# design.net
KiCad netlist of a schematic drawn in Altium Designer
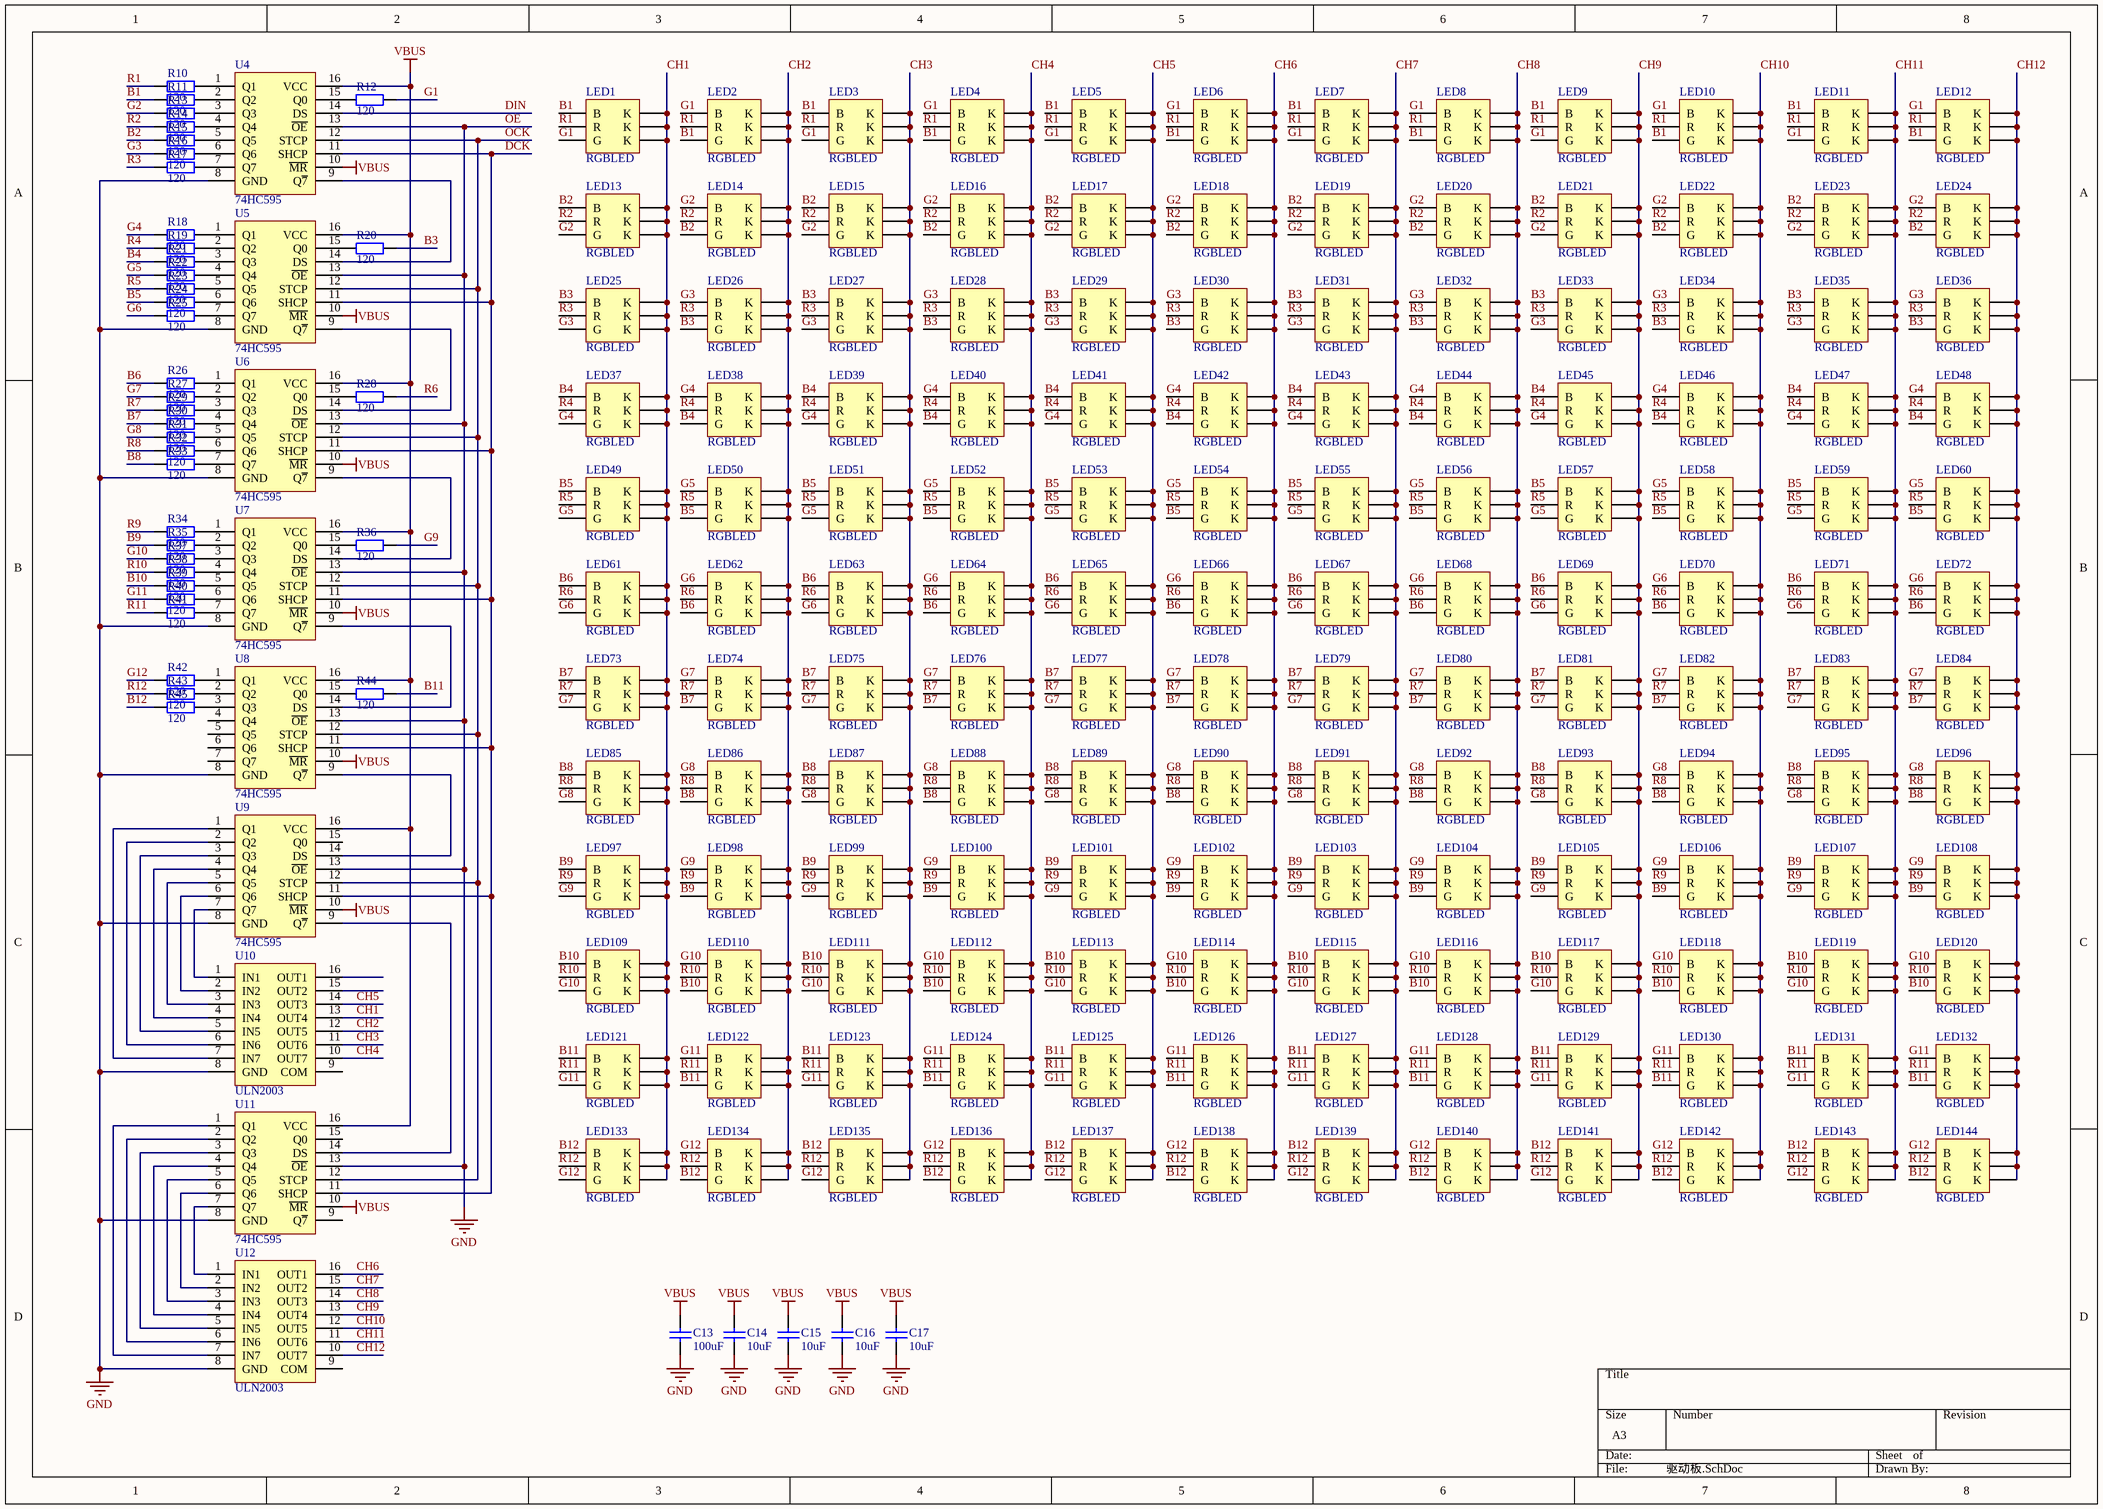
[diagram p0: 驱动板.SchDoc]

(export (version "E")
  (design (tool "Eeschema 10.0.6"))
  (components
    (comp (ref "C13")
      (value "100uF")
      (footprint "2512")
      (description "Capacitor")
      (fields (field (name "PUBLISHER") "Altium Limited"))
      (libsource (lib "yitiandelan") (part "Cap"))
    )
    (comp (ref "C14")
      (value "10uF")
      (footprint "0805")
      (description "Capacitor")
      (fields (field (name "PUBLISHER") "Altium Limited"))
      (libsource (lib "yitiandelan") (part "Cap"))
    )
    (comp (ref "C15")
      (value "10uF")
      (footprint "0805")
      (description "Capacitor")
      (fields (field (name "PUBLISHER") "Altium Limited"))
      (libsource (lib "yitiandelan") (part "Cap"))
    )
    (comp (ref "C16")
      (value "10uF")
      (footprint "0805")
      (description "Capacitor")
      (fields (field (name "PUBLISHER") "Altium Limited"))
      (libsource (lib "yitiandelan") (part "Cap"))
    )
    (comp (ref "C17")
      (value "10uF")
      (footprint "0805")
      (description "Capacitor")
      (fields (field (name "PUBLISHER") "Altium Limited"))
      (libsource (lib "yitiandelan") (part "Cap"))
    )
    (comp (ref "LED1") (value "RGBLED") (footprint "5050") (libsource (lib "yitiandelan") (part "RGBLED")))
    (comp (ref "LED2") (value "RGBLED") (footprint "5050") (libsource (lib "yitiandelan") (part "RGBLED")))
    (comp (ref "LED3") (value "RGBLED") (footprint "5050") (libsource (lib "yitiandelan") (part "RGBLED")))
    (comp (ref "LED4") (value "RGBLED") (footprint "5050") (libsource (lib "yitiandelan") (part "RGBLED")))
    (comp (ref "LED5") (value "RGBLED") (footprint "5050") (libsource (lib "yitiandelan") (part "RGBLED")))
    (comp (ref "LED6") (value "RGBLED") (footprint "5050") (libsource (lib "yitiandelan") (part "RGBLED")))
    (comp (ref "LED7") (value "RGBLED") (footprint "5050") (libsource (lib "yitiandelan") (part "RGBLED")))
    (comp (ref "LED8") (value "RGBLED") (footprint "5050") (libsource (lib "yitiandelan") (part "RGBLED")))
    (comp (ref "LED9") (value "RGBLED") (footprint "5050") (libsource (lib "yitiandelan") (part "RGBLED")))
    (comp (ref "LED10") (value "RGBLED") (footprint "5050") (libsource (lib "yitiandelan") (part "RGBLED")))
    (comp (ref "LED11") (value "RGBLED") (footprint "5050") (libsource (lib "yitiandelan") (part "RGBLED")))
    (comp (ref "LED12") (value "RGBLED") (footprint "5050") (libsource (lib "yitiandelan") (part "RGBLED")))
    (comp (ref "LED13") (value "RGBLED") (footprint "5050") (libsource (lib "yitiandelan") (part "RGBLED")))
    (comp (ref "LED14") (value "RGBLED") (footprint "5050") (libsource (lib "yitiandelan") (part "RGBLED")))
    (comp (ref "LED15") (value "RGBLED") (footprint "5050") (libsource (lib "yitiandelan") (part "RGBLED")))
    (comp (ref "LED16") (value "RGBLED") (footprint "5050") (libsource (lib "yitiandelan") (part "RGBLED")))
    (comp (ref "LED17") (value "RGBLED") (footprint "5050") (libsource (lib "yitiandelan") (part "RGBLED")))
    (comp (ref "LED18") (value "RGBLED") (footprint "5050") (libsource (lib "yitiandelan") (part "RGBLED")))
    (comp (ref "LED19") (value "RGBLED") (footprint "5050") (libsource (lib "yitiandelan") (part "RGBLED")))
    (comp (ref "LED20") (value "RGBLED") (footprint "5050") (libsource (lib "yitiandelan") (part "RGBLED")))
    (comp (ref "LED21") (value "RGBLED") (footprint "5050") (libsource (lib "yitiandelan") (part "RGBLED")))
    (comp (ref "LED22") (value "RGBLED") (footprint "5050") (libsource (lib "yitiandelan") (part "RGBLED")))
    (comp (ref "LED23") (value "RGBLED") (footprint "5050") (libsource (lib "yitiandelan") (part "RGBLED")))
    (comp (ref "LED24") (value "RGBLED") (footprint "5050") (libsource (lib "yitiandelan") (part "RGBLED")))
    (comp (ref "LED25") (value "RGBLED") (footprint "5050") (libsource (lib "yitiandelan") (part "RGBLED")))
    (comp (ref "LED26") (value "RGBLED") (footprint "5050") (libsource (lib "yitiandelan") (part "RGBLED")))
    (comp (ref "LED27") (value "RGBLED") (footprint "5050") (libsource (lib "yitiandelan") (part "RGBLED")))
    (comp (ref "LED28") (value "RGBLED") (footprint "5050") (libsource (lib "yitiandelan") (part "RGBLED")))
    (comp (ref "LED29") (value "RGBLED") (footprint "5050") (libsource (lib "yitiandelan") (part "RGBLED")))
    (comp (ref "LED30") (value "RGBLED") (footprint "5050") (libsource (lib "yitiandelan") (part "RGBLED")))
    (comp (ref "LED31") (value "RGBLED") (footprint "5050") (libsource (lib "yitiandelan") (part "RGBLED")))
    (comp (ref "LED32") (value "RGBLED") (footprint "5050") (libsource (lib "yitiandelan") (part "RGBLED")))
    (comp (ref "LED33") (value "RGBLED") (footprint "5050") (libsource (lib "yitiandelan") (part "RGBLED")))
    (comp (ref "LED34") (value "RGBLED") (footprint "5050") (libsource (lib "yitiandelan") (part "RGBLED")))
    (comp (ref "LED35") (value "RGBLED") (footprint "5050") (libsource (lib "yitiandelan") (part "RGBLED")))
    (comp (ref "LED36") (value "RGBLED") (footprint "5050") (libsource (lib "yitiandelan") (part "RGBLED")))
    (comp (ref "LED37") (value "RGBLED") (footprint "5050") (libsource (lib "yitiandelan") (part "RGBLED")))
    (comp (ref "LED38") (value "RGBLED") (footprint "5050") (libsource (lib "yitiandelan") (part "RGBLED")))
    (comp (ref "LED39") (value "RGBLED") (footprint "5050") (libsource (lib "yitiandelan") (part "RGBLED")))
    (comp (ref "LED40") (value "RGBLED") (footprint "5050") (libsource (lib "yitiandelan") (part "RGBLED")))
    (comp (ref "LED41") (value "RGBLED") (footprint "5050") (libsource (lib "yitiandelan") (part "RGBLED")))
    (comp (ref "LED42") (value "RGBLED") (footprint "5050") (libsource (lib "yitiandelan") (part "RGBLED")))
    (comp (ref "LED43") (value "RGBLED") (footprint "5050") (libsource (lib "yitiandelan") (part "RGBLED")))
    (comp (ref "LED44") (value "RGBLED") (footprint "5050") (libsource (lib "yitiandelan") (part "RGBLED")))
    (comp (ref "LED45") (value "RGBLED") (footprint "5050") (libsource (lib "yitiandelan") (part "RGBLED")))
    (comp (ref "LED46") (value "RGBLED") (footprint "5050") (libsource (lib "yitiandelan") (part "RGBLED")))
    (comp (ref "LED47") (value "RGBLED") (footprint "5050") (libsource (lib "yitiandelan") (part "RGBLED")))
    (comp (ref "LED48") (value "RGBLED") (footprint "5050") (libsource (lib "yitiandelan") (part "RGBLED")))
    (comp (ref "LED49") (value "RGBLED") (footprint "5050") (libsource (lib "yitiandelan") (part "RGBLED")))
    (comp (ref "LED50") (value "RGBLED") (footprint "5050") (libsource (lib "yitiandelan") (part "RGBLED")))
    (comp (ref "LED51") (value "RGBLED") (footprint "5050") (libsource (lib "yitiandelan") (part "RGBLED")))
    (comp (ref "LED52") (value "RGBLED") (footprint "5050") (libsource (lib "yitiandelan") (part "RGBLED")))
    (comp (ref "LED53") (value "RGBLED") (footprint "5050") (libsource (lib "yitiandelan") (part "RGBLED")))
    (comp (ref "LED54") (value "RGBLED") (footprint "5050") (libsource (lib "yitiandelan") (part "RGBLED")))
    (comp (ref "LED55") (value "RGBLED") (footprint "5050") (libsource (lib "yitiandelan") (part "RGBLED")))
    (comp (ref "LED56") (value "RGBLED") (footprint "5050") (libsource (lib "yitiandelan") (part "RGBLED")))
    (comp (ref "LED57") (value "RGBLED") (footprint "5050") (libsource (lib "yitiandelan") (part "RGBLED")))
    (comp (ref "LED58") (value "RGBLED") (footprint "5050") (libsource (lib "yitiandelan") (part "RGBLED")))
    (comp (ref "LED59") (value "RGBLED") (footprint "5050") (libsource (lib "yitiandelan") (part "RGBLED")))
    (comp (ref "LED60") (value "RGBLED") (footprint "5050") (libsource (lib "yitiandelan") (part "RGBLED")))
    (comp (ref "LED61") (value "RGBLED") (footprint "5050") (libsource (lib "yitiandelan") (part "RGBLED")))
    (comp (ref "LED62") (value "RGBLED") (footprint "5050") (libsource (lib "yitiandelan") (part "RGBLED")))
    (comp (ref "LED63") (value "RGBLED") (footprint "5050") (libsource (lib "yitiandelan") (part "RGBLED")))
    (comp (ref "LED64") (value "RGBLED") (footprint "5050") (libsource (lib "yitiandelan") (part "RGBLED")))
    (comp (ref "LED65") (value "RGBLED") (footprint "5050") (libsource (lib "yitiandelan") (part "RGBLED")))
    (comp (ref "LED66") (value "RGBLED") (footprint "5050") (libsource (lib "yitiandelan") (part "RGBLED")))
    (comp (ref "LED67") (value "RGBLED") (footprint "5050") (libsource (lib "yitiandelan") (part "RGBLED")))
    (comp (ref "LED68") (value "RGBLED") (footprint "5050") (libsource (lib "yitiandelan") (part "RGBLED")))
    (comp (ref "LED69") (value "RGBLED") (footprint "5050") (libsource (lib "yitiandelan") (part "RGBLED")))
    (comp (ref "LED70") (value "RGBLED") (footprint "5050") (libsource (lib "yitiandelan") (part "RGBLED")))
    (comp (ref "LED71") (value "RGBLED") (footprint "5050") (libsource (lib "yitiandelan") (part "RGBLED")))
    (comp (ref "LED72") (value "RGBLED") (footprint "5050") (libsource (lib "yitiandelan") (part "RGBLED")))
    (comp (ref "LED73") (value "RGBLED") (footprint "5050") (libsource (lib "yitiandelan") (part "RGBLED")))
    (comp (ref "LED74") (value "RGBLED") (footprint "5050") (libsource (lib "yitiandelan") (part "RGBLED")))
    (comp (ref "LED75") (value "RGBLED") (footprint "5050") (libsource (lib "yitiandelan") (part "RGBLED")))
    (comp (ref "LED76") (value "RGBLED") (footprint "5050") (libsource (lib "yitiandelan") (part "RGBLED")))
    (comp (ref "LED77") (value "RGBLED") (footprint "5050") (libsource (lib "yitiandelan") (part "RGBLED")))
    (comp (ref "LED78") (value "RGBLED") (footprint "5050") (libsource (lib "yitiandelan") (part "RGBLED")))
    (comp (ref "LED79") (value "RGBLED") (footprint "5050") (libsource (lib "yitiandelan") (part "RGBLED")))
    (comp (ref "LED80") (value "RGBLED") (footprint "5050") (libsource (lib "yitiandelan") (part "RGBLED")))
    (comp (ref "LED81") (value "RGBLED") (footprint "5050") (libsource (lib "yitiandelan") (part "RGBLED")))
    (comp (ref "LED82") (value "RGBLED") (footprint "5050") (libsource (lib "yitiandelan") (part "RGBLED")))
    (comp (ref "LED83") (value "RGBLED") (footprint "5050") (libsource (lib "yitiandelan") (part "RGBLED")))
    (comp (ref "LED84") (value "RGBLED") (footprint "5050") (libsource (lib "yitiandelan") (part "RGBLED")))
    (comp (ref "LED85") (value "RGBLED") (footprint "5050") (libsource (lib "yitiandelan") (part "RGBLED")))
    (comp (ref "LED86") (value "RGBLED") (footprint "5050") (libsource (lib "yitiandelan") (part "RGBLED")))
    (comp (ref "LED87") (value "RGBLED") (footprint "5050") (libsource (lib "yitiandelan") (part "RGBLED")))
    (comp (ref "LED88") (value "RGBLED") (footprint "5050") (libsource (lib "yitiandelan") (part "RGBLED")))
    (comp (ref "LED89") (value "RGBLED") (footprint "5050") (libsource (lib "yitiandelan") (part "RGBLED")))
    (comp (ref "LED90") (value "RGBLED") (footprint "5050") (libsource (lib "yitiandelan") (part "RGBLED")))
    (comp (ref "LED91") (value "RGBLED") (footprint "5050") (libsource (lib "yitiandelan") (part "RGBLED")))
    (comp (ref "LED92") (value "RGBLED") (footprint "5050") (libsource (lib "yitiandelan") (part "RGBLED")))
    (comp (ref "LED93") (value "RGBLED") (footprint "5050") (libsource (lib "yitiandelan") (part "RGBLED")))
    (comp (ref "LED94") (value "RGBLED") (footprint "5050") (libsource (lib "yitiandelan") (part "RGBLED")))
    (comp (ref "LED95") (value "RGBLED") (footprint "5050") (libsource (lib "yitiandelan") (part "RGBLED")))
    (comp (ref "LED96") (value "RGBLED") (footprint "5050") (libsource (lib "yitiandelan") (part "RGBLED")))
    (comp (ref "LED97") (value "RGBLED") (footprint "5050") (libsource (lib "yitiandelan") (part "RGBLED")))
    (comp (ref "LED98") (value "RGBLED") (footprint "5050") (libsource (lib "yitiandelan") (part "RGBLED")))
    (comp (ref "LED99") (value "RGBLED") (footprint "5050") (libsource (lib "yitiandelan") (part "RGBLED")))
    (comp (ref "LED100") (value "RGBLED") (footprint "5050") (libsource (lib "yitiandelan") (part "RGBLED")))
    (comp (ref "LED101") (value "RGBLED") (footprint "5050") (libsource (lib "yitiandelan") (part "RGBLED")))
    (comp (ref "LED102") (value "RGBLED") (footprint "5050") (libsource (lib "yitiandelan") (part "RGBLED")))
    (comp (ref "LED103") (value "RGBLED") (footprint "5050") (libsource (lib "yitiandelan") (part "RGBLED")))
    (comp (ref "LED104") (value "RGBLED") (footprint "5050") (libsource (lib "yitiandelan") (part "RGBLED")))
    (comp (ref "LED105") (value "RGBLED") (footprint "5050") (libsource (lib "yitiandelan") (part "RGBLED")))
    (comp (ref "LED106") (value "RGBLED") (footprint "5050") (libsource (lib "yitiandelan") (part "RGBLED")))
    (comp (ref "LED107") (value "RGBLED") (footprint "5050") (libsource (lib "yitiandelan") (part "RGBLED")))
    (comp (ref "LED108") (value "RGBLED") (footprint "5050") (libsource (lib "yitiandelan") (part "RGBLED")))
    (comp (ref "LED109") (value "RGBLED") (footprint "5050") (libsource (lib "yitiandelan") (part "RGBLED")))
    (comp (ref "LED110") (value "RGBLED") (footprint "5050") (libsource (lib "yitiandelan") (part "RGBLED")))
    (comp (ref "LED111") (value "RGBLED") (footprint "5050") (libsource (lib "yitiandelan") (part "RGBLED")))
    (comp (ref "LED112") (value "RGBLED") (footprint "5050") (libsource (lib "yitiandelan") (part "RGBLED")))
    (comp (ref "LED113") (value "RGBLED") (footprint "5050") (libsource (lib "yitiandelan") (part "RGBLED")))
    (comp (ref "LED114") (value "RGBLED") (footprint "5050") (libsource (lib "yitiandelan") (part "RGBLED")))
    (comp (ref "LED115") (value "RGBLED") (footprint "5050") (libsource (lib "yitiandelan") (part "RGBLED")))
    (comp (ref "LED116") (value "RGBLED") (footprint "5050") (libsource (lib "yitiandelan") (part "RGBLED")))
    (comp (ref "LED117") (value "RGBLED") (footprint "5050") (libsource (lib "yitiandelan") (part "RGBLED")))
    (comp (ref "LED118") (value "RGBLED") (footprint "5050") (libsource (lib "yitiandelan") (part "RGBLED")))
    (comp (ref "LED119") (value "RGBLED") (footprint "5050") (libsource (lib "yitiandelan") (part "RGBLED")))
    (comp (ref "LED120") (value "RGBLED") (footprint "5050") (libsource (lib "yitiandelan") (part "RGBLED")))
    (comp (ref "LED121") (value "RGBLED") (footprint "5050") (libsource (lib "yitiandelan") (part "RGBLED")))
    (comp (ref "LED122") (value "RGBLED") (footprint "5050") (libsource (lib "yitiandelan") (part "RGBLED")))
    (comp (ref "LED123") (value "RGBLED") (footprint "5050") (libsource (lib "yitiandelan") (part "RGBLED")))
    (comp (ref "LED124") (value "RGBLED") (footprint "5050") (libsource (lib "yitiandelan") (part "RGBLED")))
    (comp (ref "LED125") (value "RGBLED") (footprint "5050") (libsource (lib "yitiandelan") (part "RGBLED")))
    (comp (ref "LED126") (value "RGBLED") (footprint "5050") (libsource (lib "yitiandelan") (part "RGBLED")))
    (comp (ref "LED127") (value "RGBLED") (footprint "5050") (libsource (lib "yitiandelan") (part "RGBLED")))
    (comp (ref "LED128") (value "RGBLED") (footprint "5050") (libsource (lib "yitiandelan") (part "RGBLED")))
    (comp (ref "LED129") (value "RGBLED") (footprint "5050") (libsource (lib "yitiandelan") (part "RGBLED")))
    (comp (ref "LED130") (value "RGBLED") (footprint "5050") (libsource (lib "yitiandelan") (part "RGBLED")))
    (comp (ref "LED131") (value "RGBLED") (footprint "5050") (libsource (lib "yitiandelan") (part "RGBLED")))
    (comp (ref "LED132") (value "RGBLED") (footprint "5050") (libsource (lib "yitiandelan") (part "RGBLED")))
    (comp (ref "LED133") (value "RGBLED") (footprint "5050") (libsource (lib "yitiandelan") (part "RGBLED")))
    (comp (ref "LED134") (value "RGBLED") (footprint "5050") (libsource (lib "yitiandelan") (part "RGBLED")))
    (comp (ref "LED135") (value "RGBLED") (footprint "5050") (libsource (lib "yitiandelan") (part "RGBLED")))
    (comp (ref "LED136") (value "RGBLED") (footprint "5050") (libsource (lib "yitiandelan") (part "RGBLED")))
    (comp (ref "LED137") (value "RGBLED") (footprint "5050") (libsource (lib "yitiandelan") (part "RGBLED")))
    (comp (ref "LED138") (value "RGBLED") (footprint "5050") (libsource (lib "yitiandelan") (part "RGBLED")))
    (comp (ref "LED139") (value "RGBLED") (footprint "5050") (libsource (lib "yitiandelan") (part "RGBLED")))
    (comp (ref "LED140") (value "RGBLED") (footprint "5050") (libsource (lib "yitiandelan") (part "RGBLED")))
    (comp (ref "LED141") (value "RGBLED") (footprint "5050") (libsource (lib "yitiandelan") (part "RGBLED")))
    (comp (ref "LED142") (value "RGBLED") (footprint "5050") (libsource (lib "yitiandelan") (part "RGBLED")))
    (comp (ref "LED143") (value "RGBLED") (footprint "5050") (libsource (lib "yitiandelan") (part "RGBLED")))
    (comp (ref "LED144") (value "RGBLED") (footprint "5050") (libsource (lib "yitiandelan") (part "RGBLED")))
    (comp (ref "R10")
      (value "120")
      (footprint "0805")
      (description "Resistor")
      (fields (field (name "PUBLISHER") "Altium Limited"))
      (libsource (lib "yitiandelan") (part "Res2"))
    )
    (comp (ref "R11")
      (value "120")
      (footprint "0805")
      (description "Resistor")
      (fields (field (name "PUBLISHER") "Altium Limited"))
      (libsource (lib "yitiandelan") (part "Res2"))
    )
    (comp (ref "R12")
      (value "120")
      (footprint "0805")
      (description "Resistor")
      (fields (field (name "PUBLISHER") "Altium Limited"))
      (libsource (lib "yitiandelan") (part "Res2"))
    )
    (comp (ref "R13")
      (value "120")
      (footprint "0805")
      (description "Resistor")
      (fields (field (name "PUBLISHER") "Altium Limited"))
      (libsource (lib "yitiandelan") (part "Res2"))
    )
    (comp (ref "R14")
      (value "120")
      (footprint "0805")
      (description "Resistor")
      (fields (field (name "PUBLISHER") "Altium Limited"))
      (libsource (lib "yitiandelan") (part "Res2"))
    )
    (comp (ref "R15")
      (value "120")
      (footprint "0805")
      (description "Resistor")
      (fields (field (name "PUBLISHER") "Altium Limited"))
      (libsource (lib "yitiandelan") (part "Res2"))
    )
    (comp (ref "R16")
      (value "120")
      (footprint "0805")
      (description "Resistor")
      (fields (field (name "PUBLISHER") "Altium Limited"))
      (libsource (lib "yitiandelan") (part "Res2"))
    )
    (comp (ref "R17")
      (value "120")
      (footprint "0805")
      (description "Resistor")
      (fields (field (name "PUBLISHER") "Altium Limited"))
      (libsource (lib "yitiandelan") (part "Res2"))
    )
    (comp (ref "R18")
      (value "120")
      (footprint "0805")
      (description "Resistor")
      (fields (field (name "PUBLISHER") "Altium Limited"))
      (libsource (lib "yitiandelan") (part "Res2"))
    )
    (comp (ref "R19")
      (value "120")
      (footprint "0805")
      (description "Resistor")
      (fields (field (name "PUBLISHER") "Altium Limited"))
      (libsource (lib "yitiandelan") (part "Res2"))
    )
    (comp (ref "R20")
      (value "120")
      (footprint "0805")
      (description "Resistor")
      (fields (field (name "PUBLISHER") "Altium Limited"))
      (libsource (lib "yitiandelan") (part "Res2"))
    )
    (comp (ref "R21")
      (value "120")
      (footprint "0805")
      (description "Resistor")
      (fields (field (name "PUBLISHER") "Altium Limited"))
      (libsource (lib "yitiandelan") (part "Res2"))
    )
    (comp (ref "R22")
      (value "120")
      (footprint "0805")
      (description "Resistor")
      (fields (field (name "PUBLISHER") "Altium Limited"))
      (libsource (lib "yitiandelan") (part "Res2"))
    )
    (comp (ref "R23")
      (value "120")
      (footprint "0805")
      (description "Resistor")
      (fields (field (name "PUBLISHER") "Altium Limited"))
      (libsource (lib "yitiandelan") (part "Res2"))
    )
    (comp (ref "R24")
      (value "120")
      (footprint "0805")
      (description "Resistor")
      (fields (field (name "PUBLISHER") "Altium Limited"))
      (libsource (lib "yitiandelan") (part "Res2"))
    )
    (comp (ref "R25")
      (value "120")
      (footprint "0805")
      (description "Resistor")
      (fields (field (name "PUBLISHER") "Altium Limited"))
      (libsource (lib "yitiandelan") (part "Res2"))
    )
    (comp (ref "R26")
      (value "120")
      (footprint "0805")
      (description "Resistor")
      (fields (field (name "PUBLISHER") "Altium Limited"))
      (libsource (lib "yitiandelan") (part "Res2"))
    )
    (comp (ref "R27")
      (value "120")
      (footprint "0805")
      (description "Resistor")
      (fields (field (name "PUBLISHER") "Altium Limited"))
      (libsource (lib "yitiandelan") (part "Res2"))
    )
    (comp (ref "R28")
      (value "120")
      (footprint "0805")
      (description "Resistor")
      (fields (field (name "PUBLISHER") "Altium Limited"))
      (libsource (lib "yitiandelan") (part "Res2"))
    )
    (comp (ref "R29")
      (value "120")
      (footprint "0805")
      (description "Resistor")
      (fields (field (name "PUBLISHER") "Altium Limited"))
      (libsource (lib "yitiandelan") (part "Res2"))
    )
    (comp (ref "R30")
      (value "120")
      (footprint "0805")
      (description "Resistor")
      (fields (field (name "PUBLISHER") "Altium Limited"))
      (libsource (lib "yitiandelan") (part "Res2"))
    )
    (comp (ref "R31")
      (value "120")
      (footprint "0805")
      (description "Resistor")
      (fields (field (name "PUBLISHER") "Altium Limited"))
      (libsource (lib "yitiandelan") (part "Res2"))
    )
    (comp (ref "R32")
      (value "120")
      (footprint "0805")
      (description "Resistor")
      (fields (field (name "PUBLISHER") "Altium Limited"))
      (libsource (lib "yitiandelan") (part "Res2"))
    )
    (comp (ref "R33")
      (value "120")
      (footprint "0805")
      (description "Resistor")
      (fields (field (name "PUBLISHER") "Altium Limited"))
      (libsource (lib "yitiandelan") (part "Res2"))
    )
    (comp (ref "R34")
      (value "120")
      (footprint "0805")
      (description "Resistor")
      (fields (field (name "PUBLISHER") "Altium Limited"))
      (libsource (lib "yitiandelan") (part "Res2"))
    )
    (comp (ref "R35")
      (value "120")
      (footprint "0805")
      (description "Resistor")
      (fields (field (name "PUBLISHER") "Altium Limited"))
      (libsource (lib "yitiandelan") (part "Res2"))
    )
    (comp (ref "R36")
      (value "120")
      (footprint "0805")
      (description "Resistor")
      (fields (field (name "PUBLISHER") "Altium Limited"))
      (libsource (lib "yitiandelan") (part "Res2"))
    )
    (comp (ref "R37")
      (value "120")
      (footprint "0805")
      (description "Resistor")
      (fields (field (name "PUBLISHER") "Altium Limited"))
      (libsource (lib "yitiandelan") (part "Res2"))
    )
    (comp (ref "R38")
      (value "120")
      (footprint "0805")
      (description "Resistor")
      (fields (field (name "PUBLISHER") "Altium Limited"))
      (libsource (lib "yitiandelan") (part "Res2"))
    )
    (comp (ref "R39")
      (value "120")
      (footprint "0805")
      (description "Resistor")
      (fields (field (name "PUBLISHER") "Altium Limited"))
      (libsource (lib "yitiandelan") (part "Res2"))
    )
    (comp (ref "R40")
      (value "120")
      (footprint "0805")
      (description "Resistor")
      (fields (field (name "PUBLISHER") "Altium Limited"))
      (libsource (lib "yitiandelan") (part "Res2"))
    )
    (comp (ref "R41")
      (value "120")
      (footprint "0805")
      (description "Resistor")
      (fields (field (name "PUBLISHER") "Altium Limited"))
      (libsource (lib "yitiandelan") (part "Res2"))
    )
    (comp (ref "R42")
      (value "120")
      (footprint "0805")
      (description "Resistor")
      (fields (field (name "PUBLISHER") "Altium Limited"))
      (libsource (lib "yitiandelan") (part "Res2"))
    )
    (comp (ref "R43")
      (value "120")
      (footprint "0805")
      (description "Resistor")
      (fields (field (name "PUBLISHER") "Altium Limited"))
      (libsource (lib "yitiandelan") (part "Res2"))
    )
    (comp (ref "R44")
      (value "120")
      (footprint "0805")
      (description "Resistor")
      (fields (field (name "PUBLISHER") "Altium Limited"))
      (libsource (lib "yitiandelan") (part "Res2"))
    )
    (comp (ref "R45")
      (value "120")
      (footprint "0805")
      (description "Resistor")
      (fields (field (name "PUBLISHER") "Altium Limited"))
      (libsource (lib "yitiandelan") (part "Res2"))
    )
    (comp (ref "U4") (value "74HC595") (footprint "SO-16_N") (libsource (lib "yitiandelan") (part "74HC595")))
    (comp (ref "U5") (value "74HC595") (footprint "SO-16_N") (libsource (lib "yitiandelan") (part "74HC595")))
    (comp (ref "U6") (value "74HC595") (footprint "SO-16_N") (libsource (lib "yitiandelan") (part "74HC595")))
    (comp (ref "U7") (value "74HC595") (footprint "SO-16_N") (libsource (lib "yitiandelan") (part "74HC595")))
    (comp (ref "U8") (value "74HC595") (footprint "SO-16_N") (libsource (lib "yitiandelan") (part "74HC595")))
    (comp (ref "U9") (value "74HC595") (footprint "SO-16_N") (libsource (lib "yitiandelan") (part "74HC595")))
    (comp (ref "U10")
      (value "ULN2003")
      (footprint "SO-16_N")
      (libsource (lib "yitiandelan") (part "ULN2003"))
    )
    (comp (ref "U11")
      (value "74HC595")
      (footprint "SO-16_N")
      (libsource (lib "yitiandelan") (part "74HC595"))
    )
    (comp (ref "U12")
      (value "ULN2003")
      (footprint "SO-16_N")
      (libsource (lib "yitiandelan") (part "ULN2003"))
    )
  )
  (nets
    (net (code "1") (name "/B1") (class "Default")
      (node (ref "LED1") (pin "1") (pinfunction "B_1") (pintype "passive"))
      (node (ref "LED10") (pin "3") (pinfunction "G_3") (pintype "passive"))
      (node (ref "LED11") (pin "1") (pinfunction "B_1") (pintype "passive"))
      (node (ref "LED12") (pin "3") (pinfunction "G_3") (pintype "passive"))
      (node (ref "LED2") (pin "3") (pinfunction "G_3") (pintype "passive"))
      (node (ref "LED3") (pin "1") (pinfunction "B_1") (pintype "passive"))
      (node (ref "LED4") (pin "3") (pinfunction "G_3") (pintype "passive"))
      (node (ref "LED5") (pin "1") (pinfunction "B_1") (pintype "passive"))
      (node (ref "LED6") (pin "3") (pinfunction "G_3") (pintype "passive"))
      (node (ref "LED7") (pin "1") (pinfunction "B_1") (pintype "passive"))
      (node (ref "LED8") (pin "3") (pinfunction "G_3") (pintype "passive"))
      (node (ref "LED9") (pin "1") (pinfunction "B_1") (pintype "passive"))
      (node (ref "R11") (pin "1") (pinfunction "1_1") (pintype "passive"))
    )
    (net (code "2") (name "/B2") (class "Default")
      (node (ref "LED13") (pin "1") (pinfunction "B_1") (pintype "passive"))
      (node (ref "LED14") (pin "3") (pinfunction "G_3") (pintype "passive"))
      (node (ref "LED15") (pin "1") (pinfunction "B_1") (pintype "passive"))
      (node (ref "LED16") (pin "3") (pinfunction "G_3") (pintype "passive"))
      (node (ref "LED17") (pin "1") (pinfunction "B_1") (pintype "passive"))
      (node (ref "LED18") (pin "3") (pinfunction "G_3") (pintype "passive"))
      (node (ref "LED19") (pin "1") (pinfunction "B_1") (pintype "passive"))
      (node (ref "LED20") (pin "3") (pinfunction "G_3") (pintype "passive"))
      (node (ref "LED21") (pin "1") (pinfunction "B_1") (pintype "passive"))
      (node (ref "LED22") (pin "3") (pinfunction "G_3") (pintype "passive"))
      (node (ref "LED23") (pin "1") (pinfunction "B_1") (pintype "passive"))
      (node (ref "LED24") (pin "3") (pinfunction "G_3") (pintype "passive"))
      (node (ref "R15") (pin "1") (pinfunction "1_1") (pintype "passive"))
    )
    (net (code "3") (name "/B3") (class "Default")
      (node (ref "LED25") (pin "1") (pinfunction "B_1") (pintype "passive"))
      (node (ref "LED26") (pin "3") (pinfunction "G_3") (pintype "passive"))
      (node (ref "LED27") (pin "1") (pinfunction "B_1") (pintype "passive"))
      (node (ref "LED28") (pin "3") (pinfunction "G_3") (pintype "passive"))
      (node (ref "LED29") (pin "1") (pinfunction "B_1") (pintype "passive"))
      (node (ref "LED30") (pin "3") (pinfunction "G_3") (pintype "passive"))
      (node (ref "LED31") (pin "1") (pinfunction "B_1") (pintype "passive"))
      (node (ref "LED32") (pin "3") (pinfunction "G_3") (pintype "passive"))
      (node (ref "LED33") (pin "1") (pinfunction "B_1") (pintype "passive"))
      (node (ref "LED34") (pin "3") (pinfunction "G_3") (pintype "passive"))
      (node (ref "LED35") (pin "1") (pinfunction "B_1") (pintype "passive"))
      (node (ref "LED36") (pin "3") (pinfunction "G_3") (pintype "passive"))
      (node (ref "R20") (pin "2") (pinfunction "2_2") (pintype "passive"))
    )
    (net (code "4") (name "/B4") (class "Default")
      (node (ref "LED37") (pin "1") (pinfunction "B_1") (pintype "passive"))
      (node (ref "LED38") (pin "3") (pinfunction "G_3") (pintype "passive"))
      (node (ref "LED39") (pin "1") (pinfunction "B_1") (pintype "passive"))
      (node (ref "LED40") (pin "3") (pinfunction "G_3") (pintype "passive"))
      (node (ref "LED41") (pin "1") (pinfunction "B_1") (pintype "passive"))
      (node (ref "LED42") (pin "3") (pinfunction "G_3") (pintype "passive"))
      (node (ref "LED43") (pin "1") (pinfunction "B_1") (pintype "passive"))
      (node (ref "LED44") (pin "3") (pinfunction "G_3") (pintype "passive"))
      (node (ref "LED45") (pin "1") (pinfunction "B_1") (pintype "passive"))
      (node (ref "LED46") (pin "3") (pinfunction "G_3") (pintype "passive"))
      (node (ref "LED47") (pin "1") (pinfunction "B_1") (pintype "passive"))
      (node (ref "LED48") (pin "3") (pinfunction "G_3") (pintype "passive"))
      (node (ref "R21") (pin "1") (pinfunction "1_1") (pintype "passive"))
    )
    (net (code "5") (name "/B5") (class "Default")
      (node (ref "LED49") (pin "1") (pinfunction "B_1") (pintype "passive"))
      (node (ref "LED50") (pin "3") (pinfunction "G_3") (pintype "passive"))
      (node (ref "LED51") (pin "1") (pinfunction "B_1") (pintype "passive"))
      (node (ref "LED52") (pin "3") (pinfunction "G_3") (pintype "passive"))
      (node (ref "LED53") (pin "1") (pinfunction "B_1") (pintype "passive"))
      (node (ref "LED54") (pin "3") (pinfunction "G_3") (pintype "passive"))
      (node (ref "LED55") (pin "1") (pinfunction "B_1") (pintype "passive"))
      (node (ref "LED56") (pin "3") (pinfunction "G_3") (pintype "passive"))
      (node (ref "LED57") (pin "1") (pinfunction "B_1") (pintype "passive"))
      (node (ref "LED58") (pin "3") (pinfunction "G_3") (pintype "passive"))
      (node (ref "LED59") (pin "1") (pinfunction "B_1") (pintype "passive"))
      (node (ref "LED60") (pin "3") (pinfunction "G_3") (pintype "passive"))
      (node (ref "R24") (pin "1") (pinfunction "1_1") (pintype "passive"))
    )
    (net (code "6") (name "/B6") (class "Default")
      (node (ref "LED61") (pin "1") (pinfunction "B_1") (pintype "passive"))
      (node (ref "LED62") (pin "3") (pinfunction "G_3") (pintype "passive"))
      (node (ref "LED63") (pin "1") (pinfunction "B_1") (pintype "passive"))
      (node (ref "LED64") (pin "3") (pinfunction "G_3") (pintype "passive"))
      (node (ref "LED65") (pin "1") (pinfunction "B_1") (pintype "passive"))
      (node (ref "LED66") (pin "3") (pinfunction "G_3") (pintype "passive"))
      (node (ref "LED67") (pin "1") (pinfunction "B_1") (pintype "passive"))
      (node (ref "LED68") (pin "3") (pinfunction "G_3") (pintype "passive"))
      (node (ref "LED69") (pin "1") (pinfunction "B_1") (pintype "passive"))
      (node (ref "LED70") (pin "3") (pinfunction "G_3") (pintype "passive"))
      (node (ref "LED71") (pin "1") (pinfunction "B_1") (pintype "passive"))
      (node (ref "LED72") (pin "3") (pinfunction "G_3") (pintype "passive"))
      (node (ref "R26") (pin "1") (pinfunction "1_1") (pintype "passive"))
    )
    (net (code "7") (name "/B7") (class "Default")
      (node (ref "LED73") (pin "1") (pinfunction "B_1") (pintype "passive"))
      (node (ref "LED74") (pin "3") (pinfunction "G_3") (pintype "passive"))
      (node (ref "LED75") (pin "1") (pinfunction "B_1") (pintype "passive"))
      (node (ref "LED76") (pin "3") (pinfunction "G_3") (pintype "passive"))
      (node (ref "LED77") (pin "1") (pinfunction "B_1") (pintype "passive"))
      (node (ref "LED78") (pin "3") (pinfunction "G_3") (pintype "passive"))
      (node (ref "LED79") (pin "1") (pinfunction "B_1") (pintype "passive"))
      (node (ref "LED80") (pin "3") (pinfunction "G_3") (pintype "passive"))
      (node (ref "LED81") (pin "1") (pinfunction "B_1") (pintype "passive"))
      (node (ref "LED82") (pin "3") (pinfunction "G_3") (pintype "passive"))
      (node (ref "LED83") (pin "1") (pinfunction "B_1") (pintype "passive"))
      (node (ref "LED84") (pin "3") (pinfunction "G_3") (pintype "passive"))
      (node (ref "R30") (pin "1") (pinfunction "1_1") (pintype "passive"))
    )
    (net (code "8") (name "/B8") (class "Default")
      (node (ref "LED85") (pin "1") (pinfunction "B_1") (pintype "passive"))
      (node (ref "LED86") (pin "3") (pinfunction "G_3") (pintype "passive"))
      (node (ref "LED87") (pin "1") (pinfunction "B_1") (pintype "passive"))
      (node (ref "LED88") (pin "3") (pinfunction "G_3") (pintype "passive"))
      (node (ref "LED89") (pin "1") (pinfunction "B_1") (pintype "passive"))
      (node (ref "LED90") (pin "3") (pinfunction "G_3") (pintype "passive"))
      (node (ref "LED91") (pin "1") (pinfunction "B_1") (pintype "passive"))
      (node (ref "LED92") (pin "3") (pinfunction "G_3") (pintype "passive"))
      (node (ref "LED93") (pin "1") (pinfunction "B_1") (pintype "passive"))
      (node (ref "LED94") (pin "3") (pinfunction "G_3") (pintype "passive"))
      (node (ref "LED95") (pin "1") (pinfunction "B_1") (pintype "passive"))
      (node (ref "LED96") (pin "3") (pinfunction "G_3") (pintype "passive"))
      (node (ref "R33") (pin "1") (pinfunction "1_1") (pintype "passive"))
    )
    (net (code "9") (name "/B9") (class "Default")
      (node (ref "LED100") (pin "3") (pinfunction "G_3") (pintype "passive"))
      (node (ref "LED101") (pin "1") (pinfunction "B_1") (pintype "passive"))
      (node (ref "LED102") (pin "3") (pinfunction "G_3") (pintype "passive"))
      (node (ref "LED103") (pin "1") (pinfunction "B_1") (pintype "passive"))
      (node (ref "LED104") (pin "3") (pinfunction "G_3") (pintype "passive"))
      (node (ref "LED105") (pin "1") (pinfunction "B_1") (pintype "passive"))
      (node (ref "LED106") (pin "3") (pinfunction "G_3") (pintype "passive"))
      (node (ref "LED107") (pin "1") (pinfunction "B_1") (pintype "passive"))
      (node (ref "LED108") (pin "3") (pinfunction "G_3") (pintype "passive"))
      (node (ref "LED97") (pin "1") (pinfunction "B_1") (pintype "passive"))
      (node (ref "LED98") (pin "3") (pinfunction "G_3") (pintype "passive"))
      (node (ref "LED99") (pin "1") (pinfunction "B_1") (pintype "passive"))
      (node (ref "R35") (pin "1") (pinfunction "1_1") (pintype "passive"))
    )
    (net (code "10") (name "/B10") (class "Default")
      (node (ref "LED109") (pin "1") (pinfunction "B_1") (pintype "passive"))
      (node (ref "LED110") (pin "3") (pinfunction "G_3") (pintype "passive"))
      (node (ref "LED111") (pin "1") (pinfunction "B_1") (pintype "passive"))
      (node (ref "LED112") (pin "3") (pinfunction "G_3") (pintype "passive"))
      (node (ref "LED113") (pin "1") (pinfunction "B_1") (pintype "passive"))
      (node (ref "LED114") (pin "3") (pinfunction "G_3") (pintype "passive"))
      (node (ref "LED115") (pin "1") (pinfunction "B_1") (pintype "passive"))
      (node (ref "LED116") (pin "3") (pinfunction "G_3") (pintype "passive"))
      (node (ref "LED117") (pin "1") (pinfunction "B_1") (pintype "passive"))
      (node (ref "LED118") (pin "3") (pinfunction "G_3") (pintype "passive"))
      (node (ref "LED119") (pin "1") (pinfunction "B_1") (pintype "passive"))
      (node (ref "LED120") (pin "3") (pinfunction "G_3") (pintype "passive"))
      (node (ref "R39") (pin "1") (pinfunction "1_1") (pintype "passive"))
    )
    (net (code "11") (name "/B11") (class "Default")
      (node (ref "LED121") (pin "1") (pinfunction "B_1") (pintype "passive"))
      (node (ref "LED122") (pin "3") (pinfunction "G_3") (pintype "passive"))
      (node (ref "LED123") (pin "1") (pinfunction "B_1") (pintype "passive"))
      (node (ref "LED124") (pin "3") (pinfunction "G_3") (pintype "passive"))
      (node (ref "LED125") (pin "1") (pinfunction "B_1") (pintype "passive"))
      (node (ref "LED126") (pin "3") (pinfunction "G_3") (pintype "passive"))
      (node (ref "LED127") (pin "1") (pinfunction "B_1") (pintype "passive"))
      (node (ref "LED128") (pin "3") (pinfunction "G_3") (pintype "passive"))
      (node (ref "LED129") (pin "1") (pinfunction "B_1") (pintype "passive"))
      (node (ref "LED130") (pin "3") (pinfunction "G_3") (pintype "passive"))
      (node (ref "LED131") (pin "1") (pinfunction "B_1") (pintype "passive"))
      (node (ref "LED132") (pin "3") (pinfunction "G_3") (pintype "passive"))
      (node (ref "R44") (pin "2") (pinfunction "2_2") (pintype "passive"))
    )
    (net (code "12") (name "/B12") (class "Default")
      (node (ref "LED133") (pin "1") (pinfunction "B_1") (pintype "passive"))
      (node (ref "LED134") (pin "3") (pinfunction "G_3") (pintype "passive"))
      (node (ref "LED135") (pin "1") (pinfunction "B_1") (pintype "passive"))
      (node (ref "LED136") (pin "3") (pinfunction "G_3") (pintype "passive"))
      (node (ref "LED137") (pin "1") (pinfunction "B_1") (pintype "passive"))
      (node (ref "LED138") (pin "3") (pinfunction "G_3") (pintype "passive"))
      (node (ref "LED139") (pin "1") (pinfunction "B_1") (pintype "passive"))
      (node (ref "LED140") (pin "3") (pinfunction "G_3") (pintype "passive"))
      (node (ref "LED141") (pin "1") (pinfunction "B_1") (pintype "passive"))
      (node (ref "LED142") (pin "3") (pinfunction "G_3") (pintype "passive"))
      (node (ref "LED143") (pin "1") (pinfunction "B_1") (pintype "passive"))
      (node (ref "LED144") (pin "3") (pinfunction "G_3") (pintype "passive"))
      (node (ref "R45") (pin "1") (pinfunction "1_1") (pintype "passive"))
    )
    (net (code "13") (name "/CH1") (class "Default")
      (node (ref "LED1") (pin "4") (pinfunction "K_4") (pintype "passive"))
      (node (ref "LED1") (pin "5") (pinfunction "K_5") (pintype "passive"))
      (node (ref "LED1") (pin "6") (pinfunction "K_6") (pintype "passive"))
      (node (ref "LED109") (pin "4") (pinfunction "K_4") (pintype "passive"))
      (node (ref "LED109") (pin "5") (pinfunction "K_5") (pintype "passive"))
      (node (ref "LED109") (pin "6") (pinfunction "K_6") (pintype "passive"))
      (node (ref "LED121") (pin "4") (pinfunction "K_4") (pintype "passive"))
      (node (ref "LED121") (pin "5") (pinfunction "K_5") (pintype "passive"))
      (node (ref "LED121") (pin "6") (pinfunction "K_6") (pintype "passive"))
      (node (ref "LED13") (pin "4") (pinfunction "K_4") (pintype "passive"))
      (node (ref "LED13") (pin "5") (pinfunction "K_5") (pintype "passive"))
      (node (ref "LED13") (pin "6") (pinfunction "K_6") (pintype "passive"))
      (node (ref "LED133") (pin "4") (pinfunction "K_4") (pintype "passive"))
      (node (ref "LED133") (pin "5") (pinfunction "K_5") (pintype "passive"))
      (node (ref "LED133") (pin "6") (pinfunction "K_6") (pintype "passive"))
      (node (ref "LED25") (pin "4") (pinfunction "K_4") (pintype "passive"))
      (node (ref "LED25") (pin "5") (pinfunction "K_5") (pintype "passive"))
      (node (ref "LED25") (pin "6") (pinfunction "K_6") (pintype "passive"))
      (node (ref "LED37") (pin "4") (pinfunction "K_4") (pintype "passive"))
      (node (ref "LED37") (pin "5") (pinfunction "K_5") (pintype "passive"))
      (node (ref "LED37") (pin "6") (pinfunction "K_6") (pintype "passive"))
      (node (ref "LED49") (pin "4") (pinfunction "K_4") (pintype "passive"))
      (node (ref "LED49") (pin "5") (pinfunction "K_5") (pintype "passive"))
      (node (ref "LED49") (pin "6") (pinfunction "K_6") (pintype "passive"))
      (node (ref "LED61") (pin "4") (pinfunction "K_4") (pintype "passive"))
      (node (ref "LED61") (pin "5") (pinfunction "K_5") (pintype "passive"))
      (node (ref "LED61") (pin "6") (pinfunction "K_6") (pintype "passive"))
      (node (ref "LED73") (pin "4") (pinfunction "K_4") (pintype "passive"))
      (node (ref "LED73") (pin "5") (pinfunction "K_5") (pintype "passive"))
      (node (ref "LED73") (pin "6") (pinfunction "K_6") (pintype "passive"))
      (node (ref "LED85") (pin "4") (pinfunction "K_4") (pintype "passive"))
      (node (ref "LED85") (pin "5") (pinfunction "K_5") (pintype "passive"))
      (node (ref "LED85") (pin "6") (pinfunction "K_6") (pintype "passive"))
      (node (ref "LED97") (pin "4") (pinfunction "K_4") (pintype "passive"))
      (node (ref "LED97") (pin "5") (pinfunction "K_5") (pintype "passive"))
      (node (ref "LED97") (pin "6") (pinfunction "K_6") (pintype "passive"))
      (node (ref "U10") (pin "13") (pinfunction "OUT4_13") (pintype "passive"))
    )
    (net (code "14") (name "/CH2") (class "Default")
      (node (ref "LED110") (pin "4") (pinfunction "K_4") (pintype "passive"))
      (node (ref "LED110") (pin "5") (pinfunction "K_5") (pintype "passive"))
      (node (ref "LED110") (pin "6") (pinfunction "K_6") (pintype "passive"))
      (node (ref "LED122") (pin "4") (pinfunction "K_4") (pintype "passive"))
      (node (ref "LED122") (pin "5") (pinfunction "K_5") (pintype "passive"))
      (node (ref "LED122") (pin "6") (pinfunction "K_6") (pintype "passive"))
      (node (ref "LED134") (pin "4") (pinfunction "K_4") (pintype "passive"))
      (node (ref "LED134") (pin "5") (pinfunction "K_5") (pintype "passive"))
      (node (ref "LED134") (pin "6") (pinfunction "K_6") (pintype "passive"))
      (node (ref "LED14") (pin "4") (pinfunction "K_4") (pintype "passive"))
      (node (ref "LED14") (pin "5") (pinfunction "K_5") (pintype "passive"))
      (node (ref "LED14") (pin "6") (pinfunction "K_6") (pintype "passive"))
      (node (ref "LED2") (pin "4") (pinfunction "K_4") (pintype "passive"))
      (node (ref "LED2") (pin "5") (pinfunction "K_5") (pintype "passive"))
      (node (ref "LED2") (pin "6") (pinfunction "K_6") (pintype "passive"))
      (node (ref "LED26") (pin "4") (pinfunction "K_4") (pintype "passive"))
      (node (ref "LED26") (pin "5") (pinfunction "K_5") (pintype "passive"))
      (node (ref "LED26") (pin "6") (pinfunction "K_6") (pintype "passive"))
      (node (ref "LED38") (pin "4") (pinfunction "K_4") (pintype "passive"))
      (node (ref "LED38") (pin "5") (pinfunction "K_5") (pintype "passive"))
      (node (ref "LED38") (pin "6") (pinfunction "K_6") (pintype "passive"))
      (node (ref "LED50") (pin "4") (pinfunction "K_4") (pintype "passive"))
      (node (ref "LED50") (pin "5") (pinfunction "K_5") (pintype "passive"))
      (node (ref "LED50") (pin "6") (pinfunction "K_6") (pintype "passive"))
      (node (ref "LED62") (pin "4") (pinfunction "K_4") (pintype "passive"))
      (node (ref "LED62") (pin "5") (pinfunction "K_5") (pintype "passive"))
      (node (ref "LED62") (pin "6") (pinfunction "K_6") (pintype "passive"))
      (node (ref "LED74") (pin "4") (pinfunction "K_4") (pintype "passive"))
      (node (ref "LED74") (pin "5") (pinfunction "K_5") (pintype "passive"))
      (node (ref "LED74") (pin "6") (pinfunction "K_6") (pintype "passive"))
      (node (ref "LED86") (pin "4") (pinfunction "K_4") (pintype "passive"))
      (node (ref "LED86") (pin "5") (pinfunction "K_5") (pintype "passive"))
      (node (ref "LED86") (pin "6") (pinfunction "K_6") (pintype "passive"))
      (node (ref "LED98") (pin "4") (pinfunction "K_4") (pintype "passive"))
      (node (ref "LED98") (pin "5") (pinfunction "K_5") (pintype "passive"))
      (node (ref "LED98") (pin "6") (pinfunction "K_6") (pintype "passive"))
      (node (ref "U10") (pin "12") (pinfunction "OUT5_12") (pintype "passive"))
    )
    (net (code "15") (name "/CH3") (class "Default")
      (node (ref "LED111") (pin "4") (pinfunction "K_4") (pintype "passive"))
      (node (ref "LED111") (pin "5") (pinfunction "K_5") (pintype "passive"))
      (node (ref "LED111") (pin "6") (pinfunction "K_6") (pintype "passive"))
      (node (ref "LED123") (pin "4") (pinfunction "K_4") (pintype "passive"))
      (node (ref "LED123") (pin "5") (pinfunction "K_5") (pintype "passive"))
      (node (ref "LED123") (pin "6") (pinfunction "K_6") (pintype "passive"))
      (node (ref "LED135") (pin "4") (pinfunction "K_4") (pintype "passive"))
      (node (ref "LED135") (pin "5") (pinfunction "K_5") (pintype "passive"))
      (node (ref "LED135") (pin "6") (pinfunction "K_6") (pintype "passive"))
      (node (ref "LED15") (pin "4") (pinfunction "K_4") (pintype "passive"))
      (node (ref "LED15") (pin "5") (pinfunction "K_5") (pintype "passive"))
      (node (ref "LED15") (pin "6") (pinfunction "K_6") (pintype "passive"))
      (node (ref "LED27") (pin "4") (pinfunction "K_4") (pintype "passive"))
      (node (ref "LED27") (pin "5") (pinfunction "K_5") (pintype "passive"))
      (node (ref "LED27") (pin "6") (pinfunction "K_6") (pintype "passive"))
      (node (ref "LED3") (pin "4") (pinfunction "K_4") (pintype "passive"))
      (node (ref "LED3") (pin "5") (pinfunction "K_5") (pintype "passive"))
      (node (ref "LED3") (pin "6") (pinfunction "K_6") (pintype "passive"))
      (node (ref "LED39") (pin "4") (pinfunction "K_4") (pintype "passive"))
      (node (ref "LED39") (pin "5") (pinfunction "K_5") (pintype "passive"))
      (node (ref "LED39") (pin "6") (pinfunction "K_6") (pintype "passive"))
      (node (ref "LED51") (pin "4") (pinfunction "K_4") (pintype "passive"))
      (node (ref "LED51") (pin "5") (pinfunction "K_5") (pintype "passive"))
      (node (ref "LED51") (pin "6") (pinfunction "K_6") (pintype "passive"))
      (node (ref "LED63") (pin "4") (pinfunction "K_4") (pintype "passive"))
      (node (ref "LED63") (pin "5") (pinfunction "K_5") (pintype "passive"))
      (node (ref "LED63") (pin "6") (pinfunction "K_6") (pintype "passive"))
      (node (ref "LED75") (pin "4") (pinfunction "K_4") (pintype "passive"))
      (node (ref "LED75") (pin "5") (pinfunction "K_5") (pintype "passive"))
      (node (ref "LED75") (pin "6") (pinfunction "K_6") (pintype "passive"))
      (node (ref "LED87") (pin "4") (pinfunction "K_4") (pintype "passive"))
      (node (ref "LED87") (pin "5") (pinfunction "K_5") (pintype "passive"))
      (node (ref "LED87") (pin "6") (pinfunction "K_6") (pintype "passive"))
      (node (ref "LED99") (pin "4") (pinfunction "K_4") (pintype "passive"))
      (node (ref "LED99") (pin "5") (pinfunction "K_5") (pintype "passive"))
      (node (ref "LED99") (pin "6") (pinfunction "K_6") (pintype "passive"))
      (node (ref "U10") (pin "11") (pinfunction "OUT6_11") (pintype "passive"))
    )
    (net (code "16") (name "/CH4") (class "Default")
      (node (ref "LED100") (pin "4") (pinfunction "K_4") (pintype "passive"))
      (node (ref "LED100") (pin "5") (pinfunction "K_5") (pintype "passive"))
      (node (ref "LED100") (pin "6") (pinfunction "K_6") (pintype "passive"))
      (node (ref "LED112") (pin "4") (pinfunction "K_4") (pintype "passive"))
      (node (ref "LED112") (pin "5") (pinfunction "K_5") (pintype "passive"))
      (node (ref "LED112") (pin "6") (pinfunction "K_6") (pintype "passive"))
      (node (ref "LED124") (pin "4") (pinfunction "K_4") (pintype "passive"))
      (node (ref "LED124") (pin "5") (pinfunction "K_5") (pintype "passive"))
      (node (ref "LED124") (pin "6") (pinfunction "K_6") (pintype "passive"))
      (node (ref "LED136") (pin "4") (pinfunction "K_4") (pintype "passive"))
      (node (ref "LED136") (pin "5") (pinfunction "K_5") (pintype "passive"))
      (node (ref "LED136") (pin "6") (pinfunction "K_6") (pintype "passive"))
      (node (ref "LED16") (pin "4") (pinfunction "K_4") (pintype "passive"))
      (node (ref "LED16") (pin "5") (pinfunction "K_5") (pintype "passive"))
      (node (ref "LED16") (pin "6") (pinfunction "K_6") (pintype "passive"))
      (node (ref "LED28") (pin "4") (pinfunction "K_4") (pintype "passive"))
      (node (ref "LED28") (pin "5") (pinfunction "K_5") (pintype "passive"))
      (node (ref "LED28") (pin "6") (pinfunction "K_6") (pintype "passive"))
      (node (ref "LED4") (pin "4") (pinfunction "K_4") (pintype "passive"))
      (node (ref "LED4") (pin "5") (pinfunction "K_5") (pintype "passive"))
      (node (ref "LED4") (pin "6") (pinfunction "K_6") (pintype "passive"))
      (node (ref "LED40") (pin "4") (pinfunction "K_4") (pintype "passive"))
      (node (ref "LED40") (pin "5") (pinfunction "K_5") (pintype "passive"))
      (node (ref "LED40") (pin "6") (pinfunction "K_6") (pintype "passive"))
      (node (ref "LED52") (pin "4") (pinfunction "K_4") (pintype "passive"))
      (node (ref "LED52") (pin "5") (pinfunction "K_5") (pintype "passive"))
      (node (ref "LED52") (pin "6") (pinfunction "K_6") (pintype "passive"))
      (node (ref "LED64") (pin "4") (pinfunction "K_4") (pintype "passive"))
      (node (ref "LED64") (pin "5") (pinfunction "K_5") (pintype "passive"))
      (node (ref "LED64") (pin "6") (pinfunction "K_6") (pintype "passive"))
      (node (ref "LED76") (pin "4") (pinfunction "K_4") (pintype "passive"))
      (node (ref "LED76") (pin "5") (pinfunction "K_5") (pintype "passive"))
      (node (ref "LED76") (pin "6") (pinfunction "K_6") (pintype "passive"))
      (node (ref "LED88") (pin "4") (pinfunction "K_4") (pintype "passive"))
      (node (ref "LED88") (pin "5") (pinfunction "K_5") (pintype "passive"))
      (node (ref "LED88") (pin "6") (pinfunction "K_6") (pintype "passive"))
      (node (ref "U10") (pin "10") (pinfunction "OUT7_10") (pintype "passive"))
    )
    (net (code "17") (name "/CH5") (class "Default")
      (node (ref "LED101") (pin "4") (pinfunction "K_4") (pintype "passive"))
      (node (ref "LED101") (pin "5") (pinfunction "K_5") (pintype "passive"))
      (node (ref "LED101") (pin "6") (pinfunction "K_6") (pintype "passive"))
      (node (ref "LED113") (pin "4") (pinfunction "K_4") (pintype "passive"))
      (node (ref "LED113") (pin "5") (pinfunction "K_5") (pintype "passive"))
      (node (ref "LED113") (pin "6") (pinfunction "K_6") (pintype "passive"))
      (node (ref "LED125") (pin "4") (pinfunction "K_4") (pintype "passive"))
      (node (ref "LED125") (pin "5") (pinfunction "K_5") (pintype "passive"))
      (node (ref "LED125") (pin "6") (pinfunction "K_6") (pintype "passive"))
      (node (ref "LED137") (pin "4") (pinfunction "K_4") (pintype "passive"))
      (node (ref "LED137") (pin "5") (pinfunction "K_5") (pintype "passive"))
      (node (ref "LED137") (pin "6") (pinfunction "K_6") (pintype "passive"))
      (node (ref "LED17") (pin "4") (pinfunction "K_4") (pintype "passive"))
      (node (ref "LED17") (pin "5") (pinfunction "K_5") (pintype "passive"))
      (node (ref "LED17") (pin "6") (pinfunction "K_6") (pintype "passive"))
      (node (ref "LED29") (pin "4") (pinfunction "K_4") (pintype "passive"))
      (node (ref "LED29") (pin "5") (pinfunction "K_5") (pintype "passive"))
      (node (ref "LED29") (pin "6") (pinfunction "K_6") (pintype "passive"))
      (node (ref "LED41") (pin "4") (pinfunction "K_4") (pintype "passive"))
      (node (ref "LED41") (pin "5") (pinfunction "K_5") (pintype "passive"))
      (node (ref "LED41") (pin "6") (pinfunction "K_6") (pintype "passive"))
      (node (ref "LED5") (pin "4") (pinfunction "K_4") (pintype "passive"))
      (node (ref "LED5") (pin "5") (pinfunction "K_5") (pintype "passive"))
      (node (ref "LED5") (pin "6") (pinfunction "K_6") (pintype "passive"))
      (node (ref "LED53") (pin "4") (pinfunction "K_4") (pintype "passive"))
      (node (ref "LED53") (pin "5") (pinfunction "K_5") (pintype "passive"))
      (node (ref "LED53") (pin "6") (pinfunction "K_6") (pintype "passive"))
      (node (ref "LED65") (pin "4") (pinfunction "K_4") (pintype "passive"))
      (node (ref "LED65") (pin "5") (pinfunction "K_5") (pintype "passive"))
      (node (ref "LED65") (pin "6") (pinfunction "K_6") (pintype "passive"))
      (node (ref "LED77") (pin "4") (pinfunction "K_4") (pintype "passive"))
      (node (ref "LED77") (pin "5") (pinfunction "K_5") (pintype "passive"))
      (node (ref "LED77") (pin "6") (pinfunction "K_6") (pintype "passive"))
      (node (ref "LED89") (pin "4") (pinfunction "K_4") (pintype "passive"))
      (node (ref "LED89") (pin "5") (pinfunction "K_5") (pintype "passive"))
      (node (ref "LED89") (pin "6") (pinfunction "K_6") (pintype "passive"))
      (node (ref "U10") (pin "14") (pinfunction "OUT3_14") (pintype "passive"))
    )
    (net (code "18") (name "/CH6") (class "Default")
      (node (ref "LED102") (pin "4") (pinfunction "K_4") (pintype "passive"))
      (node (ref "LED102") (pin "5") (pinfunction "K_5") (pintype "passive"))
      (node (ref "LED102") (pin "6") (pinfunction "K_6") (pintype "passive"))
      (node (ref "LED114") (pin "4") (pinfunction "K_4") (pintype "passive"))
      (node (ref "LED114") (pin "5") (pinfunction "K_5") (pintype "passive"))
      (node (ref "LED114") (pin "6") (pinfunction "K_6") (pintype "passive"))
      (node (ref "LED126") (pin "4") (pinfunction "K_4") (pintype "passive"))
      (node (ref "LED126") (pin "5") (pinfunction "K_5") (pintype "passive"))
      (node (ref "LED126") (pin "6") (pinfunction "K_6") (pintype "passive"))
      (node (ref "LED138") (pin "4") (pinfunction "K_4") (pintype "passive"))
      (node (ref "LED138") (pin "5") (pinfunction "K_5") (pintype "passive"))
      (node (ref "LED138") (pin "6") (pinfunction "K_6") (pintype "passive"))
      (node (ref "LED18") (pin "4") (pinfunction "K_4") (pintype "passive"))
      (node (ref "LED18") (pin "5") (pinfunction "K_5") (pintype "passive"))
      (node (ref "LED18") (pin "6") (pinfunction "K_6") (pintype "passive"))
      (node (ref "LED30") (pin "4") (pinfunction "K_4") (pintype "passive"))
      (node (ref "LED30") (pin "5") (pinfunction "K_5") (pintype "passive"))
      (node (ref "LED30") (pin "6") (pinfunction "K_6") (pintype "passive"))
      (node (ref "LED42") (pin "4") (pinfunction "K_4") (pintype "passive"))
      (node (ref "LED42") (pin "5") (pinfunction "K_5") (pintype "passive"))
      (node (ref "LED42") (pin "6") (pinfunction "K_6") (pintype "passive"))
      (node (ref "LED54") (pin "4") (pinfunction "K_4") (pintype "passive"))
      (node (ref "LED54") (pin "5") (pinfunction "K_5") (pintype "passive"))
      (node (ref "LED54") (pin "6") (pinfunction "K_6") (pintype "passive"))
      (node (ref "LED6") (pin "4") (pinfunction "K_4") (pintype "passive"))
      (node (ref "LED6") (pin "5") (pinfunction "K_5") (pintype "passive"))
      (node (ref "LED6") (pin "6") (pinfunction "K_6") (pintype "passive"))
      (node (ref "LED66") (pin "4") (pinfunction "K_4") (pintype "passive"))
      (node (ref "LED66") (pin "5") (pinfunction "K_5") (pintype "passive"))
      (node (ref "LED66") (pin "6") (pinfunction "K_6") (pintype "passive"))
      (node (ref "LED78") (pin "4") (pinfunction "K_4") (pintype "passive"))
      (node (ref "LED78") (pin "5") (pinfunction "K_5") (pintype "passive"))
      (node (ref "LED78") (pin "6") (pinfunction "K_6") (pintype "passive"))
      (node (ref "LED90") (pin "4") (pinfunction "K_4") (pintype "passive"))
      (node (ref "LED90") (pin "5") (pinfunction "K_5") (pintype "passive"))
      (node (ref "LED90") (pin "6") (pinfunction "K_6") (pintype "passive"))
      (node (ref "U12") (pin "16") (pinfunction "OUT1_16") (pintype "passive"))
    )
    (net (code "19") (name "/CH7") (class "Default")
      (node (ref "LED103") (pin "4") (pinfunction "K_4") (pintype "passive"))
      (node (ref "LED103") (pin "5") (pinfunction "K_5") (pintype "passive"))
      (node (ref "LED103") (pin "6") (pinfunction "K_6") (pintype "passive"))
      (node (ref "LED115") (pin "4") (pinfunction "K_4") (pintype "passive"))
      (node (ref "LED115") (pin "5") (pinfunction "K_5") (pintype "passive"))
      (node (ref "LED115") (pin "6") (pinfunction "K_6") (pintype "passive"))
      (node (ref "LED127") (pin "4") (pinfunction "K_4") (pintype "passive"))
      (node (ref "LED127") (pin "5") (pinfunction "K_5") (pintype "passive"))
      (node (ref "LED127") (pin "6") (pinfunction "K_6") (pintype "passive"))
      (node (ref "LED139") (pin "4") (pinfunction "K_4") (pintype "passive"))
      (node (ref "LED139") (pin "5") (pinfunction "K_5") (pintype "passive"))
      (node (ref "LED139") (pin "6") (pinfunction "K_6") (pintype "passive"))
      (node (ref "LED19") (pin "4") (pinfunction "K_4") (pintype "passive"))
      (node (ref "LED19") (pin "5") (pinfunction "K_5") (pintype "passive"))
      (node (ref "LED19") (pin "6") (pinfunction "K_6") (pintype "passive"))
      (node (ref "LED31") (pin "4") (pinfunction "K_4") (pintype "passive"))
      (node (ref "LED31") (pin "5") (pinfunction "K_5") (pintype "passive"))
      (node (ref "LED31") (pin "6") (pinfunction "K_6") (pintype "passive"))
      (node (ref "LED43") (pin "4") (pinfunction "K_4") (pintype "passive"))
      (node (ref "LED43") (pin "5") (pinfunction "K_5") (pintype "passive"))
      (node (ref "LED43") (pin "6") (pinfunction "K_6") (pintype "passive"))
      (node (ref "LED55") (pin "4") (pinfunction "K_4") (pintype "passive"))
      (node (ref "LED55") (pin "5") (pinfunction "K_5") (pintype "passive"))
      (node (ref "LED55") (pin "6") (pinfunction "K_6") (pintype "passive"))
      (node (ref "LED67") (pin "4") (pinfunction "K_4") (pintype "passive"))
      (node (ref "LED67") (pin "5") (pinfunction "K_5") (pintype "passive"))
      (node (ref "LED67") (pin "6") (pinfunction "K_6") (pintype "passive"))
      (node (ref "LED7") (pin "4") (pinfunction "K_4") (pintype "passive"))
      (node (ref "LED7") (pin "5") (pinfunction "K_5") (pintype "passive"))
      (node (ref "LED7") (pin "6") (pinfunction "K_6") (pintype "passive"))
      (node (ref "LED79") (pin "4") (pinfunction "K_4") (pintype "passive"))
      (node (ref "LED79") (pin "5") (pinfunction "K_5") (pintype "passive"))
      (node (ref "LED79") (pin "6") (pinfunction "K_6") (pintype "passive"))
      (node (ref "LED91") (pin "4") (pinfunction "K_4") (pintype "passive"))
      (node (ref "LED91") (pin "5") (pinfunction "K_5") (pintype "passive"))
      (node (ref "LED91") (pin "6") (pinfunction "K_6") (pintype "passive"))
      (node (ref "U12") (pin "15") (pinfunction "OUT2_15") (pintype "passive"))
    )
    (net (code "20") (name "/CH8") (class "Default")
      (node (ref "LED104") (pin "4") (pinfunction "K_4") (pintype "passive"))
      (node (ref "LED104") (pin "5") (pinfunction "K_5") (pintype "passive"))
      (node (ref "LED104") (pin "6") (pinfunction "K_6") (pintype "passive"))
      (node (ref "LED116") (pin "4") (pinfunction "K_4") (pintype "passive"))
      (node (ref "LED116") (pin "5") (pinfunction "K_5") (pintype "passive"))
      (node (ref "LED116") (pin "6") (pinfunction "K_6") (pintype "passive"))
      (node (ref "LED128") (pin "4") (pinfunction "K_4") (pintype "passive"))
      (node (ref "LED128") (pin "5") (pinfunction "K_5") (pintype "passive"))
      (node (ref "LED128") (pin "6") (pinfunction "K_6") (pintype "passive"))
      (node (ref "LED140") (pin "4") (pinfunction "K_4") (pintype "passive"))
      (node (ref "LED140") (pin "5") (pinfunction "K_5") (pintype "passive"))
      (node (ref "LED140") (pin "6") (pinfunction "K_6") (pintype "passive"))
      (node (ref "LED20") (pin "4") (pinfunction "K_4") (pintype "passive"))
      (node (ref "LED20") (pin "5") (pinfunction "K_5") (pintype "passive"))
      (node (ref "LED20") (pin "6") (pinfunction "K_6") (pintype "passive"))
      (node (ref "LED32") (pin "4") (pinfunction "K_4") (pintype "passive"))
      (node (ref "LED32") (pin "5") (pinfunction "K_5") (pintype "passive"))
      (node (ref "LED32") (pin "6") (pinfunction "K_6") (pintype "passive"))
      (node (ref "LED44") (pin "4") (pinfunction "K_4") (pintype "passive"))
      (node (ref "LED44") (pin "5") (pinfunction "K_5") (pintype "passive"))
      (node (ref "LED44") (pin "6") (pinfunction "K_6") (pintype "passive"))
      (node (ref "LED56") (pin "4") (pinfunction "K_4") (pintype "passive"))
      (node (ref "LED56") (pin "5") (pinfunction "K_5") (pintype "passive"))
      (node (ref "LED56") (pin "6") (pinfunction "K_6") (pintype "passive"))
      (node (ref "LED68") (pin "4") (pinfunction "K_4") (pintype "passive"))
      (node (ref "LED68") (pin "5") (pinfunction "K_5") (pintype "passive"))
      (node (ref "LED68") (pin "6") (pinfunction "K_6") (pintype "passive"))
      (node (ref "LED8") (pin "4") (pinfunction "K_4") (pintype "passive"))
      (node (ref "LED8") (pin "5") (pinfunction "K_5") (pintype "passive"))
      (node (ref "LED8") (pin "6") (pinfunction "K_6") (pintype "passive"))
      (node (ref "LED80") (pin "4") (pinfunction "K_4") (pintype "passive"))
      (node (ref "LED80") (pin "5") (pinfunction "K_5") (pintype "passive"))
      (node (ref "LED80") (pin "6") (pinfunction "K_6") (pintype "passive"))
      (node (ref "LED92") (pin "4") (pinfunction "K_4") (pintype "passive"))
      (node (ref "LED92") (pin "5") (pinfunction "K_5") (pintype "passive"))
      (node (ref "LED92") (pin "6") (pinfunction "K_6") (pintype "passive"))
      (node (ref "U12") (pin "14") (pinfunction "OUT3_14") (pintype "passive"))
    )
    (net (code "21") (name "/CH9") (class "Default")
      (node (ref "LED105") (pin "4") (pinfunction "K_4") (pintype "passive"))
      (node (ref "LED105") (pin "5") (pinfunction "K_5") (pintype "passive"))
      (node (ref "LED105") (pin "6") (pinfunction "K_6") (pintype "passive"))
      (node (ref "LED117") (pin "4") (pinfunction "K_4") (pintype "passive"))
      (node (ref "LED117") (pin "5") (pinfunction "K_5") (pintype "passive"))
      (node (ref "LED117") (pin "6") (pinfunction "K_6") (pintype "passive"))
      (node (ref "LED129") (pin "4") (pinfunction "K_4") (pintype "passive"))
      (node (ref "LED129") (pin "5") (pinfunction "K_5") (pintype "passive"))
      (node (ref "LED129") (pin "6") (pinfunction "K_6") (pintype "passive"))
      (node (ref "LED141") (pin "4") (pinfunction "K_4") (pintype "passive"))
      (node (ref "LED141") (pin "5") (pinfunction "K_5") (pintype "passive"))
      (node (ref "LED141") (pin "6") (pinfunction "K_6") (pintype "passive"))
      (node (ref "LED21") (pin "4") (pinfunction "K_4") (pintype "passive"))
      (node (ref "LED21") (pin "5") (pinfunction "K_5") (pintype "passive"))
      (node (ref "LED21") (pin "6") (pinfunction "K_6") (pintype "passive"))
      (node (ref "LED33") (pin "4") (pinfunction "K_4") (pintype "passive"))
      (node (ref "LED33") (pin "5") (pinfunction "K_5") (pintype "passive"))
      (node (ref "LED33") (pin "6") (pinfunction "K_6") (pintype "passive"))
      (node (ref "LED45") (pin "4") (pinfunction "K_4") (pintype "passive"))
      (node (ref "LED45") (pin "5") (pinfunction "K_5") (pintype "passive"))
      (node (ref "LED45") (pin "6") (pinfunction "K_6") (pintype "passive"))
      (node (ref "LED57") (pin "4") (pinfunction "K_4") (pintype "passive"))
      (node (ref "LED57") (pin "5") (pinfunction "K_5") (pintype "passive"))
      (node (ref "LED57") (pin "6") (pinfunction "K_6") (pintype "passive"))
      (node (ref "LED69") (pin "4") (pinfunction "K_4") (pintype "passive"))
      (node (ref "LED69") (pin "5") (pinfunction "K_5") (pintype "passive"))
      (node (ref "LED69") (pin "6") (pinfunction "K_6") (pintype "passive"))
      (node (ref "LED81") (pin "4") (pinfunction "K_4") (pintype "passive"))
      (node (ref "LED81") (pin "5") (pinfunction "K_5") (pintype "passive"))
      (node (ref "LED81") (pin "6") (pinfunction "K_6") (pintype "passive"))
      (node (ref "LED9") (pin "4") (pinfunction "K_4") (pintype "passive"))
      (node (ref "LED9") (pin "5") (pinfunction "K_5") (pintype "passive"))
      (node (ref "LED9") (pin "6") (pinfunction "K_6") (pintype "passive"))
      (node (ref "LED93") (pin "4") (pinfunction "K_4") (pintype "passive"))
      (node (ref "LED93") (pin "5") (pinfunction "K_5") (pintype "passive"))
      (node (ref "LED93") (pin "6") (pinfunction "K_6") (pintype "passive"))
      (node (ref "U12") (pin "13") (pinfunction "OUT4_13") (pintype "passive"))
    )
    (net (code "22") (name "/CH10") (class "Default")
      (node (ref "LED10") (pin "4") (pinfunction "K_4") (pintype "passive"))
      (node (ref "LED10") (pin "5") (pinfunction "K_5") (pintype "passive"))
      (node (ref "LED10") (pin "6") (pinfunction "K_6") (pintype "passive"))
      (node (ref "LED106") (pin "4") (pinfunction "K_4") (pintype "passive"))
      (node (ref "LED106") (pin "5") (pinfunction "K_5") (pintype "passive"))
      (node (ref "LED106") (pin "6") (pinfunction "K_6") (pintype "passive"))
      (node (ref "LED118") (pin "4") (pinfunction "K_4") (pintype "passive"))
      (node (ref "LED118") (pin "5") (pinfunction "K_5") (pintype "passive"))
      (node (ref "LED118") (pin "6") (pinfunction "K_6") (pintype "passive"))
      (node (ref "LED130") (pin "4") (pinfunction "K_4") (pintype "passive"))
      (node (ref "LED130") (pin "5") (pinfunction "K_5") (pintype "passive"))
      (node (ref "LED130") (pin "6") (pinfunction "K_6") (pintype "passive"))
      (node (ref "LED142") (pin "4") (pinfunction "K_4") (pintype "passive"))
      (node (ref "LED142") (pin "5") (pinfunction "K_5") (pintype "passive"))
      (node (ref "LED142") (pin "6") (pinfunction "K_6") (pintype "passive"))
      (node (ref "LED22") (pin "4") (pinfunction "K_4") (pintype "passive"))
      (node (ref "LED22") (pin "5") (pinfunction "K_5") (pintype "passive"))
      (node (ref "LED22") (pin "6") (pinfunction "K_6") (pintype "passive"))
      (node (ref "LED34") (pin "4") (pinfunction "K_4") (pintype "passive"))
      (node (ref "LED34") (pin "5") (pinfunction "K_5") (pintype "passive"))
      (node (ref "LED34") (pin "6") (pinfunction "K_6") (pintype "passive"))
      (node (ref "LED46") (pin "4") (pinfunction "K_4") (pintype "passive"))
      (node (ref "LED46") (pin "5") (pinfunction "K_5") (pintype "passive"))
      (node (ref "LED46") (pin "6") (pinfunction "K_6") (pintype "passive"))
      (node (ref "LED58") (pin "4") (pinfunction "K_4") (pintype "passive"))
      (node (ref "LED58") (pin "5") (pinfunction "K_5") (pintype "passive"))
      (node (ref "LED58") (pin "6") (pinfunction "K_6") (pintype "passive"))
      (node (ref "LED70") (pin "4") (pinfunction "K_4") (pintype "passive"))
      (node (ref "LED70") (pin "5") (pinfunction "K_5") (pintype "passive"))
      (node (ref "LED70") (pin "6") (pinfunction "K_6") (pintype "passive"))
      (node (ref "LED82") (pin "4") (pinfunction "K_4") (pintype "passive"))
      (node (ref "LED82") (pin "5") (pinfunction "K_5") (pintype "passive"))
      (node (ref "LED82") (pin "6") (pinfunction "K_6") (pintype "passive"))
      (node (ref "LED94") (pin "4") (pinfunction "K_4") (pintype "passive"))
      (node (ref "LED94") (pin "5") (pinfunction "K_5") (pintype "passive"))
      (node (ref "LED94") (pin "6") (pinfunction "K_6") (pintype "passive"))
      (node (ref "U12") (pin "12") (pinfunction "OUT5_12") (pintype "passive"))
    )
    (net (code "23") (name "/CH11") (class "Default")
      (node (ref "LED107") (pin "4") (pinfunction "K_4") (pintype "passive"))
      (node (ref "LED107") (pin "5") (pinfunction "K_5") (pintype "passive"))
      (node (ref "LED107") (pin "6") (pinfunction "K_6") (pintype "passive"))
      (node (ref "LED11") (pin "4") (pinfunction "K_4") (pintype "passive"))
      (node (ref "LED11") (pin "5") (pinfunction "K_5") (pintype "passive"))
      (node (ref "LED11") (pin "6") (pinfunction "K_6") (pintype "passive"))
      (node (ref "LED119") (pin "4") (pinfunction "K_4") (pintype "passive"))
      (node (ref "LED119") (pin "5") (pinfunction "K_5") (pintype "passive"))
      (node (ref "LED119") (pin "6") (pinfunction "K_6") (pintype "passive"))
      (node (ref "LED131") (pin "4") (pinfunction "K_4") (pintype "passive"))
      (node (ref "LED131") (pin "5") (pinfunction "K_5") (pintype "passive"))
      (node (ref "LED131") (pin "6") (pinfunction "K_6") (pintype "passive"))
      (node (ref "LED143") (pin "4") (pinfunction "K_4") (pintype "passive"))
      (node (ref "LED143") (pin "5") (pinfunction "K_5") (pintype "passive"))
      (node (ref "LED143") (pin "6") (pinfunction "K_6") (pintype "passive"))
      (node (ref "LED23") (pin "4") (pinfunction "K_4") (pintype "passive"))
      (node (ref "LED23") (pin "5") (pinfunction "K_5") (pintype "passive"))
      (node (ref "LED23") (pin "6") (pinfunction "K_6") (pintype "passive"))
      (node (ref "LED35") (pin "4") (pinfunction "K_4") (pintype "passive"))
      (node (ref "LED35") (pin "5") (pinfunction "K_5") (pintype "passive"))
      (node (ref "LED35") (pin "6") (pinfunction "K_6") (pintype "passive"))
      (node (ref "LED47") (pin "4") (pinfunction "K_4") (pintype "passive"))
      (node (ref "LED47") (pin "5") (pinfunction "K_5") (pintype "passive"))
      (node (ref "LED47") (pin "6") (pinfunction "K_6") (pintype "passive"))
      (node (ref "LED59") (pin "4") (pinfunction "K_4") (pintype "passive"))
      (node (ref "LED59") (pin "5") (pinfunction "K_5") (pintype "passive"))
      (node (ref "LED59") (pin "6") (pinfunction "K_6") (pintype "passive"))
      (node (ref "LED71") (pin "4") (pinfunction "K_4") (pintype "passive"))
      (node (ref "LED71") (pin "5") (pinfunction "K_5") (pintype "passive"))
      (node (ref "LED71") (pin "6") (pinfunction "K_6") (pintype "passive"))
      (node (ref "LED83") (pin "4") (pinfunction "K_4") (pintype "passive"))
      (node (ref "LED83") (pin "5") (pinfunction "K_5") (pintype "passive"))
      (node (ref "LED83") (pin "6") (pinfunction "K_6") (pintype "passive"))
      (node (ref "LED95") (pin "4") (pinfunction "K_4") (pintype "passive"))
      (node (ref "LED95") (pin "5") (pinfunction "K_5") (pintype "passive"))
      (node (ref "LED95") (pin "6") (pinfunction "K_6") (pintype "passive"))
      (node (ref "U12") (pin "11") (pinfunction "OUT6_11") (pintype "passive"))
    )
    (net (code "24") (name "/CH12") (class "Default")
      (node (ref "LED108") (pin "4") (pinfunction "K_4") (pintype "passive"))
      (node (ref "LED108") (pin "5") (pinfunction "K_5") (pintype "passive"))
      (node (ref "LED108") (pin "6") (pinfunction "K_6") (pintype "passive"))
      (node (ref "LED12") (pin "4") (pinfunction "K_4") (pintype "passive"))
      (node (ref "LED12") (pin "5") (pinfunction "K_5") (pintype "passive"))
      (node (ref "LED12") (pin "6") (pinfunction "K_6") (pintype "passive"))
      (node (ref "LED120") (pin "4") (pinfunction "K_4") (pintype "passive"))
      (node (ref "LED120") (pin "5") (pinfunction "K_5") (pintype "passive"))
      (node (ref "LED120") (pin "6") (pinfunction "K_6") (pintype "passive"))
      (node (ref "LED132") (pin "4") (pinfunction "K_4") (pintype "passive"))
      (node (ref "LED132") (pin "5") (pinfunction "K_5") (pintype "passive"))
      (node (ref "LED132") (pin "6") (pinfunction "K_6") (pintype "passive"))
      (node (ref "LED144") (pin "4") (pinfunction "K_4") (pintype "passive"))
      (node (ref "LED144") (pin "5") (pinfunction "K_5") (pintype "passive"))
      (node (ref "LED144") (pin "6") (pinfunction "K_6") (pintype "passive"))
      (node (ref "LED24") (pin "4") (pinfunction "K_4") (pintype "passive"))
      (node (ref "LED24") (pin "5") (pinfunction "K_5") (pintype "passive"))
      (node (ref "LED24") (pin "6") (pinfunction "K_6") (pintype "passive"))
      (node (ref "LED36") (pin "4") (pinfunction "K_4") (pintype "passive"))
      (node (ref "LED36") (pin "5") (pinfunction "K_5") (pintype "passive"))
      (node (ref "LED36") (pin "6") (pinfunction "K_6") (pintype "passive"))
      (node (ref "LED48") (pin "4") (pinfunction "K_4") (pintype "passive"))
      (node (ref "LED48") (pin "5") (pinfunction "K_5") (pintype "passive"))
      (node (ref "LED48") (pin "6") (pinfunction "K_6") (pintype "passive"))
      (node (ref "LED60") (pin "4") (pinfunction "K_4") (pintype "passive"))
      (node (ref "LED60") (pin "5") (pinfunction "K_5") (pintype "passive"))
      (node (ref "LED60") (pin "6") (pinfunction "K_6") (pintype "passive"))
      (node (ref "LED72") (pin "4") (pinfunction "K_4") (pintype "passive"))
      (node (ref "LED72") (pin "5") (pinfunction "K_5") (pintype "passive"))
      (node (ref "LED72") (pin "6") (pinfunction "K_6") (pintype "passive"))
      (node (ref "LED84") (pin "4") (pinfunction "K_4") (pintype "passive"))
      (node (ref "LED84") (pin "5") (pinfunction "K_5") (pintype "passive"))
      (node (ref "LED84") (pin "6") (pinfunction "K_6") (pintype "passive"))
      (node (ref "LED96") (pin "4") (pinfunction "K_4") (pintype "passive"))
      (node (ref "LED96") (pin "5") (pinfunction "K_5") (pintype "passive"))
      (node (ref "LED96") (pin "6") (pinfunction "K_6") (pintype "passive"))
      (node (ref "U12") (pin "10") (pinfunction "OUT7_10") (pintype "passive"))
    )
    (net (code "25") (name "/DCK") (class "Default")
      (node (ref "U11") (pin "11") (pinfunction "SHCP_11") (pintype "passive"))
      (node (ref "U4") (pin "11") (pinfunction "SHCP_11") (pintype "passive"))
      (node (ref "U5") (pin "11") (pinfunction "SHCP_11") (pintype "passive"))
      (node (ref "U6") (pin "11") (pinfunction "SHCP_11") (pintype "passive"))
      (node (ref "U7") (pin "11") (pinfunction "SHCP_11") (pintype "passive"))
      (node (ref "U8") (pin "11") (pinfunction "SHCP_11") (pintype "passive"))
      (node (ref "U9") (pin "11") (pinfunction "SHCP_11") (pintype "passive"))
    )
    (net (code "26") (name "/DIN") (class "Default")
      (node (ref "U4") (pin "14") (pinfunction "DS_14") (pintype "passive"))
    )
    (net (code "27") (name "/G1") (class "Default")
      (node (ref "LED1") (pin "3") (pinfunction "G_3") (pintype "passive"))
      (node (ref "LED10") (pin "1") (pinfunction "B_1") (pintype "passive"))
      (node (ref "LED11") (pin "3") (pinfunction "G_3") (pintype "passive"))
      (node (ref "LED12") (pin "1") (pinfunction "B_1") (pintype "passive"))
      (node (ref "LED2") (pin "1") (pinfunction "B_1") (pintype "passive"))
      (node (ref "LED3") (pin "3") (pinfunction "G_3") (pintype "passive"))
      (node (ref "LED4") (pin "1") (pinfunction "B_1") (pintype "passive"))
      (node (ref "LED5") (pin "3") (pinfunction "G_3") (pintype "passive"))
      (node (ref "LED6") (pin "1") (pinfunction "B_1") (pintype "passive"))
      (node (ref "LED7") (pin "3") (pinfunction "G_3") (pintype "passive"))
      (node (ref "LED8") (pin "1") (pinfunction "B_1") (pintype "passive"))
      (node (ref "LED9") (pin "3") (pinfunction "G_3") (pintype "passive"))
      (node (ref "R12") (pin "2") (pinfunction "2_2") (pintype "passive"))
    )
    (net (code "28") (name "/G2") (class "Default")
      (node (ref "LED13") (pin "3") (pinfunction "G_3") (pintype "passive"))
      (node (ref "LED14") (pin "1") (pinfunction "B_1") (pintype "passive"))
      (node (ref "LED15") (pin "3") (pinfunction "G_3") (pintype "passive"))
      (node (ref "LED16") (pin "1") (pinfunction "B_1") (pintype "passive"))
      (node (ref "LED17") (pin "3") (pinfunction "G_3") (pintype "passive"))
      (node (ref "LED18") (pin "1") (pinfunction "B_1") (pintype "passive"))
      (node (ref "LED19") (pin "3") (pinfunction "G_3") (pintype "passive"))
      (node (ref "LED20") (pin "1") (pinfunction "B_1") (pintype "passive"))
      (node (ref "LED21") (pin "3") (pinfunction "G_3") (pintype "passive"))
      (node (ref "LED22") (pin "1") (pinfunction "B_1") (pintype "passive"))
      (node (ref "LED23") (pin "3") (pinfunction "G_3") (pintype "passive"))
      (node (ref "LED24") (pin "1") (pinfunction "B_1") (pintype "passive"))
      (node (ref "R13") (pin "1") (pinfunction "1_1") (pintype "passive"))
    )
    (net (code "29") (name "/G3") (class "Default")
      (node (ref "LED25") (pin "3") (pinfunction "G_3") (pintype "passive"))
      (node (ref "LED26") (pin "1") (pinfunction "B_1") (pintype "passive"))
      (node (ref "LED27") (pin "3") (pinfunction "G_3") (pintype "passive"))
      (node (ref "LED28") (pin "1") (pinfunction "B_1") (pintype "passive"))
      (node (ref "LED29") (pin "3") (pinfunction "G_3") (pintype "passive"))
      (node (ref "LED30") (pin "1") (pinfunction "B_1") (pintype "passive"))
      (node (ref "LED31") (pin "3") (pinfunction "G_3") (pintype "passive"))
      (node (ref "LED32") (pin "1") (pinfunction "B_1") (pintype "passive"))
      (node (ref "LED33") (pin "3") (pinfunction "G_3") (pintype "passive"))
      (node (ref "LED34") (pin "1") (pinfunction "B_1") (pintype "passive"))
      (node (ref "LED35") (pin "3") (pinfunction "G_3") (pintype "passive"))
      (node (ref "LED36") (pin "1") (pinfunction "B_1") (pintype "passive"))
      (node (ref "R16") (pin "1") (pinfunction "1_1") (pintype "passive"))
    )
    (net (code "30") (name "/G4") (class "Default")
      (node (ref "LED37") (pin "3") (pinfunction "G_3") (pintype "passive"))
      (node (ref "LED38") (pin "1") (pinfunction "B_1") (pintype "passive"))
      (node (ref "LED39") (pin "3") (pinfunction "G_3") (pintype "passive"))
      (node (ref "LED40") (pin "1") (pinfunction "B_1") (pintype "passive"))
      (node (ref "LED41") (pin "3") (pinfunction "G_3") (pintype "passive"))
      (node (ref "LED42") (pin "1") (pinfunction "B_1") (pintype "passive"))
      (node (ref "LED43") (pin "3") (pinfunction "G_3") (pintype "passive"))
      (node (ref "LED44") (pin "1") (pinfunction "B_1") (pintype "passive"))
      (node (ref "LED45") (pin "3") (pinfunction "G_3") (pintype "passive"))
      (node (ref "LED46") (pin "1") (pinfunction "B_1") (pintype "passive"))
      (node (ref "LED47") (pin "3") (pinfunction "G_3") (pintype "passive"))
      (node (ref "LED48") (pin "1") (pinfunction "B_1") (pintype "passive"))
      (node (ref "R18") (pin "1") (pinfunction "1_1") (pintype "passive"))
    )
    (net (code "31") (name "/G5") (class "Default")
      (node (ref "LED49") (pin "3") (pinfunction "G_3") (pintype "passive"))
      (node (ref "LED50") (pin "1") (pinfunction "B_1") (pintype "passive"))
      (node (ref "LED51") (pin "3") (pinfunction "G_3") (pintype "passive"))
      (node (ref "LED52") (pin "1") (pinfunction "B_1") (pintype "passive"))
      (node (ref "LED53") (pin "3") (pinfunction "G_3") (pintype "passive"))
      (node (ref "LED54") (pin "1") (pinfunction "B_1") (pintype "passive"))
      (node (ref "LED55") (pin "3") (pinfunction "G_3") (pintype "passive"))
      (node (ref "LED56") (pin "1") (pinfunction "B_1") (pintype "passive"))
      (node (ref "LED57") (pin "3") (pinfunction "G_3") (pintype "passive"))
      (node (ref "LED58") (pin "1") (pinfunction "B_1") (pintype "passive"))
      (node (ref "LED59") (pin "3") (pinfunction "G_3") (pintype "passive"))
      (node (ref "LED60") (pin "1") (pinfunction "B_1") (pintype "passive"))
      (node (ref "R22") (pin "1") (pinfunction "1_1") (pintype "passive"))
    )
    (net (code "32") (name "/G6") (class "Default")
      (node (ref "LED61") (pin "3") (pinfunction "G_3") (pintype "passive"))
      (node (ref "LED62") (pin "1") (pinfunction "B_1") (pintype "passive"))
      (node (ref "LED63") (pin "3") (pinfunction "G_3") (pintype "passive"))
      (node (ref "LED64") (pin "1") (pinfunction "B_1") (pintype "passive"))
      (node (ref "LED65") (pin "3") (pinfunction "G_3") (pintype "passive"))
      (node (ref "LED66") (pin "1") (pinfunction "B_1") (pintype "passive"))
      (node (ref "LED67") (pin "3") (pinfunction "G_3") (pintype "passive"))
      (node (ref "LED68") (pin "1") (pinfunction "B_1") (pintype "passive"))
      (node (ref "LED69") (pin "3") (pinfunction "G_3") (pintype "passive"))
      (node (ref "LED70") (pin "1") (pinfunction "B_1") (pintype "passive"))
      (node (ref "LED71") (pin "3") (pinfunction "G_3") (pintype "passive"))
      (node (ref "LED72") (pin "1") (pinfunction "B_1") (pintype "passive"))
      (node (ref "R25") (pin "1") (pinfunction "1_1") (pintype "passive"))
    )
    (net (code "33") (name "/G7") (class "Default")
      (node (ref "LED73") (pin "3") (pinfunction "G_3") (pintype "passive"))
      (node (ref "LED74") (pin "1") (pinfunction "B_1") (pintype "passive"))
      (node (ref "LED75") (pin "3") (pinfunction "G_3") (pintype "passive"))
      (node (ref "LED76") (pin "1") (pinfunction "B_1") (pintype "passive"))
      (node (ref "LED77") (pin "3") (pinfunction "G_3") (pintype "passive"))
      (node (ref "LED78") (pin "1") (pinfunction "B_1") (pintype "passive"))
      (node (ref "LED79") (pin "3") (pinfunction "G_3") (pintype "passive"))
      (node (ref "LED80") (pin "1") (pinfunction "B_1") (pintype "passive"))
      (node (ref "LED81") (pin "3") (pinfunction "G_3") (pintype "passive"))
      (node (ref "LED82") (pin "1") (pinfunction "B_1") (pintype "passive"))
      (node (ref "LED83") (pin "3") (pinfunction "G_3") (pintype "passive"))
      (node (ref "LED84") (pin "1") (pinfunction "B_1") (pintype "passive"))
      (node (ref "R27") (pin "1") (pinfunction "1_1") (pintype "passive"))
    )
    (net (code "34") (name "/G8") (class "Default")
      (node (ref "LED85") (pin "3") (pinfunction "G_3") (pintype "passive"))
      (node (ref "LED86") (pin "1") (pinfunction "B_1") (pintype "passive"))
      (node (ref "LED87") (pin "3") (pinfunction "G_3") (pintype "passive"))
      (node (ref "LED88") (pin "1") (pinfunction "B_1") (pintype "passive"))
      (node (ref "LED89") (pin "3") (pinfunction "G_3") (pintype "passive"))
      (node (ref "LED90") (pin "1") (pinfunction "B_1") (pintype "passive"))
      (node (ref "LED91") (pin "3") (pinfunction "G_3") (pintype "passive"))
      (node (ref "LED92") (pin "1") (pinfunction "B_1") (pintype "passive"))
      (node (ref "LED93") (pin "3") (pinfunction "G_3") (pintype "passive"))
      (node (ref "LED94") (pin "1") (pinfunction "B_1") (pintype "passive"))
      (node (ref "LED95") (pin "3") (pinfunction "G_3") (pintype "passive"))
      (node (ref "LED96") (pin "1") (pinfunction "B_1") (pintype "passive"))
      (node (ref "R31") (pin "1") (pinfunction "1_1") (pintype "passive"))
    )
    (net (code "35") (name "/G9") (class "Default")
      (node (ref "LED100") (pin "1") (pinfunction "B_1") (pintype "passive"))
      (node (ref "LED101") (pin "3") (pinfunction "G_3") (pintype "passive"))
      (node (ref "LED102") (pin "1") (pinfunction "B_1") (pintype "passive"))
      (node (ref "LED103") (pin "3") (pinfunction "G_3") (pintype "passive"))
      (node (ref "LED104") (pin "1") (pinfunction "B_1") (pintype "passive"))
      (node (ref "LED105") (pin "3") (pinfunction "G_3") (pintype "passive"))
      (node (ref "LED106") (pin "1") (pinfunction "B_1") (pintype "passive"))
      (node (ref "LED107") (pin "3") (pinfunction "G_3") (pintype "passive"))
      (node (ref "LED108") (pin "1") (pinfunction "B_1") (pintype "passive"))
      (node (ref "LED97") (pin "3") (pinfunction "G_3") (pintype "passive"))
      (node (ref "LED98") (pin "1") (pinfunction "B_1") (pintype "passive"))
      (node (ref "LED99") (pin "3") (pinfunction "G_3") (pintype "passive"))
      (node (ref "R36") (pin "2") (pinfunction "2_2") (pintype "passive"))
    )
    (net (code "36") (name "/G10") (class "Default")
      (node (ref "LED109") (pin "3") (pinfunction "G_3") (pintype "passive"))
      (node (ref "LED110") (pin "1") (pinfunction "B_1") (pintype "passive"))
      (node (ref "LED111") (pin "3") (pinfunction "G_3") (pintype "passive"))
      (node (ref "LED112") (pin "1") (pinfunction "B_1") (pintype "passive"))
      (node (ref "LED113") (pin "3") (pinfunction "G_3") (pintype "passive"))
      (node (ref "LED114") (pin "1") (pinfunction "B_1") (pintype "passive"))
      (node (ref "LED115") (pin "3") (pinfunction "G_3") (pintype "passive"))
      (node (ref "LED116") (pin "1") (pinfunction "B_1") (pintype "passive"))
      (node (ref "LED117") (pin "3") (pinfunction "G_3") (pintype "passive"))
      (node (ref "LED118") (pin "1") (pinfunction "B_1") (pintype "passive"))
      (node (ref "LED119") (pin "3") (pinfunction "G_3") (pintype "passive"))
      (node (ref "LED120") (pin "1") (pinfunction "B_1") (pintype "passive"))
      (node (ref "R37") (pin "1") (pinfunction "1_1") (pintype "passive"))
    )
    (net (code "37") (name "/G11") (class "Default")
      (node (ref "LED121") (pin "3") (pinfunction "G_3") (pintype "passive"))
      (node (ref "LED122") (pin "1") (pinfunction "B_1") (pintype "passive"))
      (node (ref "LED123") (pin "3") (pinfunction "G_3") (pintype "passive"))
      (node (ref "LED124") (pin "1") (pinfunction "B_1") (pintype "passive"))
      (node (ref "LED125") (pin "3") (pinfunction "G_3") (pintype "passive"))
      (node (ref "LED126") (pin "1") (pinfunction "B_1") (pintype "passive"))
      (node (ref "LED127") (pin "3") (pinfunction "G_3") (pintype "passive"))
      (node (ref "LED128") (pin "1") (pinfunction "B_1") (pintype "passive"))
      (node (ref "LED129") (pin "3") (pinfunction "G_3") (pintype "passive"))
      (node (ref "LED130") (pin "1") (pinfunction "B_1") (pintype "passive"))
      (node (ref "LED131") (pin "3") (pinfunction "G_3") (pintype "passive"))
      (node (ref "LED132") (pin "1") (pinfunction "B_1") (pintype "passive"))
      (node (ref "R40") (pin "1") (pinfunction "1_1") (pintype "passive"))
    )
    (net (code "38") (name "/G12") (class "Default")
      (node (ref "LED133") (pin "3") (pinfunction "G_3") (pintype "passive"))
      (node (ref "LED134") (pin "1") (pinfunction "B_1") (pintype "passive"))
      (node (ref "LED135") (pin "3") (pinfunction "G_3") (pintype "passive"))
      (node (ref "LED136") (pin "1") (pinfunction "B_1") (pintype "passive"))
      (node (ref "LED137") (pin "3") (pinfunction "G_3") (pintype "passive"))
      (node (ref "LED138") (pin "1") (pinfunction "B_1") (pintype "passive"))
      (node (ref "LED139") (pin "3") (pinfunction "G_3") (pintype "passive"))
      (node (ref "LED140") (pin "1") (pinfunction "B_1") (pintype "passive"))
      (node (ref "LED141") (pin "3") (pinfunction "G_3") (pintype "passive"))
      (node (ref "LED142") (pin "1") (pinfunction "B_1") (pintype "passive"))
      (node (ref "LED143") (pin "3") (pinfunction "G_3") (pintype "passive"))
      (node (ref "LED144") (pin "1") (pinfunction "B_1") (pintype "passive"))
      (node (ref "R42") (pin "1") (pinfunction "1_1") (pintype "passive"))
    )
    (net (code "39") (name "/OCK") (class "Default")
      (node (ref "U11") (pin "12") (pinfunction "STCP_12") (pintype "passive"))
      (node (ref "U4") (pin "12") (pinfunction "STCP_12") (pintype "passive"))
      (node (ref "U5") (pin "12") (pinfunction "STCP_12") (pintype "passive"))
      (node (ref "U6") (pin "12") (pinfunction "STCP_12") (pintype "passive"))
      (node (ref "U7") (pin "12") (pinfunction "STCP_12") (pintype "passive"))
      (node (ref "U8") (pin "12") (pinfunction "STCP_12") (pintype "passive"))
      (node (ref "U9") (pin "12") (pinfunction "STCP_12") (pintype "passive"))
    )
    (net (code "40") (name "/R1") (class "Default")
      (node (ref "LED1") (pin "2") (pinfunction "R_2") (pintype "passive"))
      (node (ref "LED10") (pin "2") (pinfunction "R_2") (pintype "passive"))
      (node (ref "LED11") (pin "2") (pinfunction "R_2") (pintype "passive"))
      (node (ref "LED12") (pin "2") (pinfunction "R_2") (pintype "passive"))
      (node (ref "LED2") (pin "2") (pinfunction "R_2") (pintype "passive"))
      (node (ref "LED3") (pin "2") (pinfunction "R_2") (pintype "passive"))
      (node (ref "LED4") (pin "2") (pinfunction "R_2") (pintype "passive"))
      (node (ref "LED5") (pin "2") (pinfunction "R_2") (pintype "passive"))
      (node (ref "LED6") (pin "2") (pinfunction "R_2") (pintype "passive"))
      (node (ref "LED7") (pin "2") (pinfunction "R_2") (pintype "passive"))
      (node (ref "LED8") (pin "2") (pinfunction "R_2") (pintype "passive"))
      (node (ref "LED9") (pin "2") (pinfunction "R_2") (pintype "passive"))
      (node (ref "R10") (pin "1") (pinfunction "1_1") (pintype "passive"))
    )
    (net (code "41") (name "/R2") (class "Default")
      (node (ref "LED13") (pin "2") (pinfunction "R_2") (pintype "passive"))
      (node (ref "LED14") (pin "2") (pinfunction "R_2") (pintype "passive"))
      (node (ref "LED15") (pin "2") (pinfunction "R_2") (pintype "passive"))
      (node (ref "LED16") (pin "2") (pinfunction "R_2") (pintype "passive"))
      (node (ref "LED17") (pin "2") (pinfunction "R_2") (pintype "passive"))
      (node (ref "LED18") (pin "2") (pinfunction "R_2") (pintype "passive"))
      (node (ref "LED19") (pin "2") (pinfunction "R_2") (pintype "passive"))
      (node (ref "LED20") (pin "2") (pinfunction "R_2") (pintype "passive"))
      (node (ref "LED21") (pin "2") (pinfunction "R_2") (pintype "passive"))
      (node (ref "LED22") (pin "2") (pinfunction "R_2") (pintype "passive"))
      (node (ref "LED23") (pin "2") (pinfunction "R_2") (pintype "passive"))
      (node (ref "LED24") (pin "2") (pinfunction "R_2") (pintype "passive"))
      (node (ref "R14") (pin "1") (pinfunction "1_1") (pintype "passive"))
    )
    (net (code "42") (name "/R3") (class "Default")
      (node (ref "LED25") (pin "2") (pinfunction "R_2") (pintype "passive"))
      (node (ref "LED26") (pin "2") (pinfunction "R_2") (pintype "passive"))
      (node (ref "LED27") (pin "2") (pinfunction "R_2") (pintype "passive"))
      (node (ref "LED28") (pin "2") (pinfunction "R_2") (pintype "passive"))
      (node (ref "LED29") (pin "2") (pinfunction "R_2") (pintype "passive"))
      (node (ref "LED30") (pin "2") (pinfunction "R_2") (pintype "passive"))
      (node (ref "LED31") (pin "2") (pinfunction "R_2") (pintype "passive"))
      (node (ref "LED32") (pin "2") (pinfunction "R_2") (pintype "passive"))
      (node (ref "LED33") (pin "2") (pinfunction "R_2") (pintype "passive"))
      (node (ref "LED34") (pin "2") (pinfunction "R_2") (pintype "passive"))
      (node (ref "LED35") (pin "2") (pinfunction "R_2") (pintype "passive"))
      (node (ref "LED36") (pin "2") (pinfunction "R_2") (pintype "passive"))
      (node (ref "R17") (pin "1") (pinfunction "1_1") (pintype "passive"))
    )
    (net (code "43") (name "/R4") (class "Default")
      (node (ref "LED37") (pin "2") (pinfunction "R_2") (pintype "passive"))
      (node (ref "LED38") (pin "2") (pinfunction "R_2") (pintype "passive"))
      (node (ref "LED39") (pin "2") (pinfunction "R_2") (pintype "passive"))
      (node (ref "LED40") (pin "2") (pinfunction "R_2") (pintype "passive"))
      (node (ref "LED41") (pin "2") (pinfunction "R_2") (pintype "passive"))
      (node (ref "LED42") (pin "2") (pinfunction "R_2") (pintype "passive"))
      (node (ref "LED43") (pin "2") (pinfunction "R_2") (pintype "passive"))
      (node (ref "LED44") (pin "2") (pinfunction "R_2") (pintype "passive"))
      (node (ref "LED45") (pin "2") (pinfunction "R_2") (pintype "passive"))
      (node (ref "LED46") (pin "2") (pinfunction "R_2") (pintype "passive"))
      (node (ref "LED47") (pin "2") (pinfunction "R_2") (pintype "passive"))
      (node (ref "LED48") (pin "2") (pinfunction "R_2") (pintype "passive"))
      (node (ref "R19") (pin "1") (pinfunction "1_1") (pintype "passive"))
    )
    (net (code "44") (name "/R5") (class "Default")
      (node (ref "LED49") (pin "2") (pinfunction "R_2") (pintype "passive"))
      (node (ref "LED50") (pin "2") (pinfunction "R_2") (pintype "passive"))
      (node (ref "LED51") (pin "2") (pinfunction "R_2") (pintype "passive"))
      (node (ref "LED52") (pin "2") (pinfunction "R_2") (pintype "passive"))
      (node (ref "LED53") (pin "2") (pinfunction "R_2") (pintype "passive"))
      (node (ref "LED54") (pin "2") (pinfunction "R_2") (pintype "passive"))
      (node (ref "LED55") (pin "2") (pinfunction "R_2") (pintype "passive"))
      (node (ref "LED56") (pin "2") (pinfunction "R_2") (pintype "passive"))
      (node (ref "LED57") (pin "2") (pinfunction "R_2") (pintype "passive"))
      (node (ref "LED58") (pin "2") (pinfunction "R_2") (pintype "passive"))
      (node (ref "LED59") (pin "2") (pinfunction "R_2") (pintype "passive"))
      (node (ref "LED60") (pin "2") (pinfunction "R_2") (pintype "passive"))
      (node (ref "R23") (pin "1") (pinfunction "1_1") (pintype "passive"))
    )
    (net (code "45") (name "/R6") (class "Default")
      (node (ref "LED61") (pin "2") (pinfunction "R_2") (pintype "passive"))
      (node (ref "LED62") (pin "2") (pinfunction "R_2") (pintype "passive"))
      (node (ref "LED63") (pin "2") (pinfunction "R_2") (pintype "passive"))
      (node (ref "LED64") (pin "2") (pinfunction "R_2") (pintype "passive"))
      (node (ref "LED65") (pin "2") (pinfunction "R_2") (pintype "passive"))
      (node (ref "LED66") (pin "2") (pinfunction "R_2") (pintype "passive"))
      (node (ref "LED67") (pin "2") (pinfunction "R_2") (pintype "passive"))
      (node (ref "LED68") (pin "2") (pinfunction "R_2") (pintype "passive"))
      (node (ref "LED69") (pin "2") (pinfunction "R_2") (pintype "passive"))
      (node (ref "LED70") (pin "2") (pinfunction "R_2") (pintype "passive"))
      (node (ref "LED71") (pin "2") (pinfunction "R_2") (pintype "passive"))
      (node (ref "LED72") (pin "2") (pinfunction "R_2") (pintype "passive"))
      (node (ref "R28") (pin "2") (pinfunction "2_2") (pintype "passive"))
    )
    (net (code "46") (name "/R7") (class "Default")
      (node (ref "LED73") (pin "2") (pinfunction "R_2") (pintype "passive"))
      (node (ref "LED74") (pin "2") (pinfunction "R_2") (pintype "passive"))
      (node (ref "LED75") (pin "2") (pinfunction "R_2") (pintype "passive"))
      (node (ref "LED76") (pin "2") (pinfunction "R_2") (pintype "passive"))
      (node (ref "LED77") (pin "2") (pinfunction "R_2") (pintype "passive"))
      (node (ref "LED78") (pin "2") (pinfunction "R_2") (pintype "passive"))
      (node (ref "LED79") (pin "2") (pinfunction "R_2") (pintype "passive"))
      (node (ref "LED80") (pin "2") (pinfunction "R_2") (pintype "passive"))
      (node (ref "LED81") (pin "2") (pinfunction "R_2") (pintype "passive"))
      (node (ref "LED82") (pin "2") (pinfunction "R_2") (pintype "passive"))
      (node (ref "LED83") (pin "2") (pinfunction "R_2") (pintype "passive"))
      (node (ref "LED84") (pin "2") (pinfunction "R_2") (pintype "passive"))
      (node (ref "R29") (pin "1") (pinfunction "1_1") (pintype "passive"))
    )
    (net (code "47") (name "/R8") (class "Default")
      (node (ref "LED85") (pin "2") (pinfunction "R_2") (pintype "passive"))
      (node (ref "LED86") (pin "2") (pinfunction "R_2") (pintype "passive"))
      (node (ref "LED87") (pin "2") (pinfunction "R_2") (pintype "passive"))
      (node (ref "LED88") (pin "2") (pinfunction "R_2") (pintype "passive"))
      (node (ref "LED89") (pin "2") (pinfunction "R_2") (pintype "passive"))
      (node (ref "LED90") (pin "2") (pinfunction "R_2") (pintype "passive"))
      (node (ref "LED91") (pin "2") (pinfunction "R_2") (pintype "passive"))
      (node (ref "LED92") (pin "2") (pinfunction "R_2") (pintype "passive"))
      (node (ref "LED93") (pin "2") (pinfunction "R_2") (pintype "passive"))
      (node (ref "LED94") (pin "2") (pinfunction "R_2") (pintype "passive"))
      (node (ref "LED95") (pin "2") (pinfunction "R_2") (pintype "passive"))
      (node (ref "LED96") (pin "2") (pinfunction "R_2") (pintype "passive"))
      (node (ref "R32") (pin "1") (pinfunction "1_1") (pintype "passive"))
    )
    (net (code "48") (name "/R9") (class "Default")
      (node (ref "LED100") (pin "2") (pinfunction "R_2") (pintype "passive"))
      (node (ref "LED101") (pin "2") (pinfunction "R_2") (pintype "passive"))
      (node (ref "LED102") (pin "2") (pinfunction "R_2") (pintype "passive"))
      (node (ref "LED103") (pin "2") (pinfunction "R_2") (pintype "passive"))
      (node (ref "LED104") (pin "2") (pinfunction "R_2") (pintype "passive"))
      (node (ref "LED105") (pin "2") (pinfunction "R_2") (pintype "passive"))
      (node (ref "LED106") (pin "2") (pinfunction "R_2") (pintype "passive"))
      (node (ref "LED107") (pin "2") (pinfunction "R_2") (pintype "passive"))
      (node (ref "LED108") (pin "2") (pinfunction "R_2") (pintype "passive"))
      (node (ref "LED97") (pin "2") (pinfunction "R_2") (pintype "passive"))
      (node (ref "LED98") (pin "2") (pinfunction "R_2") (pintype "passive"))
      (node (ref "LED99") (pin "2") (pinfunction "R_2") (pintype "passive"))
      (node (ref "R34") (pin "1") (pinfunction "1_1") (pintype "passive"))
    )
    (net (code "49") (name "/R10") (class "Default")
      (node (ref "LED109") (pin "2") (pinfunction "R_2") (pintype "passive"))
      (node (ref "LED110") (pin "2") (pinfunction "R_2") (pintype "passive"))
      (node (ref "LED111") (pin "2") (pinfunction "R_2") (pintype "passive"))
      (node (ref "LED112") (pin "2") (pinfunction "R_2") (pintype "passive"))
      (node (ref "LED113") (pin "2") (pinfunction "R_2") (pintype "passive"))
      (node (ref "LED114") (pin "2") (pinfunction "R_2") (pintype "passive"))
      (node (ref "LED115") (pin "2") (pinfunction "R_2") (pintype "passive"))
      (node (ref "LED116") (pin "2") (pinfunction "R_2") (pintype "passive"))
      (node (ref "LED117") (pin "2") (pinfunction "R_2") (pintype "passive"))
      (node (ref "LED118") (pin "2") (pinfunction "R_2") (pintype "passive"))
      (node (ref "LED119") (pin "2") (pinfunction "R_2") (pintype "passive"))
      (node (ref "LED120") (pin "2") (pinfunction "R_2") (pintype "passive"))
      (node (ref "R38") (pin "1") (pinfunction "1_1") (pintype "passive"))
    )
    (net (code "50") (name "/R11") (class "Default")
      (node (ref "LED121") (pin "2") (pinfunction "R_2") (pintype "passive"))
      (node (ref "LED122") (pin "2") (pinfunction "R_2") (pintype "passive"))
      (node (ref "LED123") (pin "2") (pinfunction "R_2") (pintype "passive"))
      (node (ref "LED124") (pin "2") (pinfunction "R_2") (pintype "passive"))
      (node (ref "LED125") (pin "2") (pinfunction "R_2") (pintype "passive"))
      (node (ref "LED126") (pin "2") (pinfunction "R_2") (pintype "passive"))
      (node (ref "LED127") (pin "2") (pinfunction "R_2") (pintype "passive"))
      (node (ref "LED128") (pin "2") (pinfunction "R_2") (pintype "passive"))
      (node (ref "LED129") (pin "2") (pinfunction "R_2") (pintype "passive"))
      (node (ref "LED130") (pin "2") (pinfunction "R_2") (pintype "passive"))
      (node (ref "LED131") (pin "2") (pinfunction "R_2") (pintype "passive"))
      (node (ref "LED132") (pin "2") (pinfunction "R_2") (pintype "passive"))
      (node (ref "R41") (pin "1") (pinfunction "1_1") (pintype "passive"))
    )
    (net (code "51") (name "/R12") (class "Default")
      (node (ref "LED133") (pin "2") (pinfunction "R_2") (pintype "passive"))
      (node (ref "LED134") (pin "2") (pinfunction "R_2") (pintype "passive"))
      (node (ref "LED135") (pin "2") (pinfunction "R_2") (pintype "passive"))
      (node (ref "LED136") (pin "2") (pinfunction "R_2") (pintype "passive"))
      (node (ref "LED137") (pin "2") (pinfunction "R_2") (pintype "passive"))
      (node (ref "LED138") (pin "2") (pinfunction "R_2") (pintype "passive"))
      (node (ref "LED139") (pin "2") (pinfunction "R_2") (pintype "passive"))
      (node (ref "LED140") (pin "2") (pinfunction "R_2") (pintype "passive"))
      (node (ref "LED141") (pin "2") (pinfunction "R_2") (pintype "passive"))
      (node (ref "LED142") (pin "2") (pinfunction "R_2") (pintype "passive"))
      (node (ref "LED143") (pin "2") (pinfunction "R_2") (pintype "passive"))
      (node (ref "LED144") (pin "2") (pinfunction "R_2") (pintype "passive"))
      (node (ref "R43") (pin "1") (pinfunction "1_1") (pintype "passive"))
    )
    (net (code "52") (name "GND") (class "Default")
      (node (ref "C13") (pin "2") (pinfunction "2_2") (pintype "passive"))
      (node (ref "C14") (pin "2") (pinfunction "2_2") (pintype "passive"))
      (node (ref "C15") (pin "2") (pinfunction "2_2") (pintype "passive"))
      (node (ref "C16") (pin "2") (pinfunction "2_2") (pintype "passive"))
      (node (ref "C17") (pin "2") (pinfunction "2_2") (pintype "passive"))
      (node (ref "U10") (pin "8") (pinfunction "GND_8") (pintype "passive"))
      (node (ref "U11") (pin "13") (pinfunction "~{OE}_13") (pintype "passive"))
      (node (ref "U11") (pin "8") (pinfunction "GND_8") (pintype "passive"))
      (node (ref "U12") (pin "8") (pinfunction "GND_8") (pintype "passive"))
      (node (ref "U4") (pin "13") (pinfunction "~{OE}_13") (pintype "passive"))
      (node (ref "U4") (pin "8") (pinfunction "GND_8") (pintype "passive"))
      (node (ref "U5") (pin "13") (pinfunction "~{OE}_13") (pintype "passive"))
      (node (ref "U5") (pin "8") (pinfunction "GND_8") (pintype "passive"))
      (node (ref "U6") (pin "13") (pinfunction "~{OE}_13") (pintype "passive"))
      (node (ref "U6") (pin "8") (pinfunction "GND_8") (pintype "passive"))
      (node (ref "U7") (pin "13") (pinfunction "~{OE}_13") (pintype "passive"))
      (node (ref "U7") (pin "8") (pinfunction "GND_8") (pintype "passive"))
      (node (ref "U8") (pin "13") (pinfunction "~{OE}_13") (pintype "passive"))
      (node (ref "U8") (pin "8") (pinfunction "GND_8") (pintype "passive"))
      (node (ref "U9") (pin "13") (pinfunction "~{OE}_13") (pintype "passive"))
      (node (ref "U9") (pin "8") (pinfunction "GND_8") (pintype "passive"))
    )
    (net (code "53") (name "Net-(U4-Q0)") (class "Default")
      (node (ref "R12") (pin "1") (pinfunction "1_1") (pintype "passive"))
      (node (ref "U4") (pin "15") (pinfunction "Q0_15") (pintype "passive"))
    )
    (net (code "54") (name "Net-(U4-Q1)") (class "Default")
      (node (ref "R10") (pin "2") (pinfunction "2_2") (pintype "passive"))
      (node (ref "U4") (pin "1") (pinfunction "Q1_1") (pintype "passive"))
    )
    (net (code "55") (name "Net-(U4-Q2)") (class "Default")
      (node (ref "R11") (pin "2") (pinfunction "2_2") (pintype "passive"))
      (node (ref "U4") (pin "2") (pinfunction "Q2_2") (pintype "passive"))
    )
    (net (code "56") (name "Net-(U4-Q3)") (class "Default")
      (node (ref "R13") (pin "2") (pinfunction "2_2") (pintype "passive"))
      (node (ref "U4") (pin "3") (pinfunction "Q3_3") (pintype "passive"))
    )
    (net (code "57") (name "Net-(U4-Q4)") (class "Default")
      (node (ref "R14") (pin "2") (pinfunction "2_2") (pintype "passive"))
      (node (ref "U4") (pin "4") (pinfunction "Q4_4") (pintype "passive"))
    )
    (net (code "58") (name "Net-(U4-Q5)") (class "Default")
      (node (ref "R15") (pin "2") (pinfunction "2_2") (pintype "passive"))
      (node (ref "U4") (pin "5") (pinfunction "Q5_5") (pintype "passive"))
    )
    (net (code "59") (name "Net-(U4-Q6)") (class "Default")
      (node (ref "R16") (pin "2") (pinfunction "2_2") (pintype "passive"))
      (node (ref "U4") (pin "6") (pinfunction "Q6_6") (pintype "passive"))
    )
    (net (code "60") (name "Net-(U4-Q7)") (class "Default")
      (node (ref "R17") (pin "2") (pinfunction "2_2") (pintype "passive"))
      (node (ref "U4") (pin "7") (pinfunction "Q7_7") (pintype "passive"))
    )
    (net (code "61") (name "Net-(U4-Q~{7})") (class "Default")
      (node (ref "U4") (pin "9") (pinfunction "Q~{7}_9") (pintype "passive"))
      (node (ref "U5") (pin "14") (pinfunction "DS_14") (pintype "passive"))
    )
    (net (code "62") (name "Net-(U5-Q0)") (class "Default")
      (node (ref "R20") (pin "1") (pinfunction "1_1") (pintype "passive"))
      (node (ref "U5") (pin "15") (pinfunction "Q0_15") (pintype "passive"))
    )
    (net (code "63") (name "Net-(U5-Q1)") (class "Default")
      (node (ref "R18") (pin "2") (pinfunction "2_2") (pintype "passive"))
      (node (ref "U5") (pin "1") (pinfunction "Q1_1") (pintype "passive"))
    )
    (net (code "64") (name "Net-(U5-Q2)") (class "Default")
      (node (ref "R19") (pin "2") (pinfunction "2_2") (pintype "passive"))
      (node (ref "U5") (pin "2") (pinfunction "Q2_2") (pintype "passive"))
    )
    (net (code "65") (name "Net-(U5-Q3)") (class "Default")
      (node (ref "R21") (pin "2") (pinfunction "2_2") (pintype "passive"))
      (node (ref "U5") (pin "3") (pinfunction "Q3_3") (pintype "passive"))
    )
    (net (code "66") (name "Net-(U5-Q4)") (class "Default")
      (node (ref "R22") (pin "2") (pinfunction "2_2") (pintype "passive"))
      (node (ref "U5") (pin "4") (pinfunction "Q4_4") (pintype "passive"))
    )
    (net (code "67") (name "Net-(U5-Q5)") (class "Default")
      (node (ref "R23") (pin "2") (pinfunction "2_2") (pintype "passive"))
      (node (ref "U5") (pin "5") (pinfunction "Q5_5") (pintype "passive"))
    )
    (net (code "68") (name "Net-(U5-Q6)") (class "Default")
      (node (ref "R24") (pin "2") (pinfunction "2_2") (pintype "passive"))
      (node (ref "U5") (pin "6") (pinfunction "Q6_6") (pintype "passive"))
    )
    (net (code "69") (name "Net-(U5-Q7)") (class "Default")
      (node (ref "R25") (pin "2") (pinfunction "2_2") (pintype "passive"))
      (node (ref "U5") (pin "7") (pinfunction "Q7_7") (pintype "passive"))
    )
    (net (code "70") (name "Net-(U5-Q~{7})") (class "Default")
      (node (ref "U5") (pin "9") (pinfunction "Q~{7}_9") (pintype "passive"))
      (node (ref "U6") (pin "14") (pinfunction "DS_14") (pintype "passive"))
    )
    (net (code "71") (name "Net-(U6-Q0)") (class "Default")
      (node (ref "R28") (pin "1") (pinfunction "1_1") (pintype "passive"))
      (node (ref "U6") (pin "15") (pinfunction "Q0_15") (pintype "passive"))
    )
    (net (code "72") (name "Net-(U6-Q1)") (class "Default")
      (node (ref "R26") (pin "2") (pinfunction "2_2") (pintype "passive"))
      (node (ref "U6") (pin "1") (pinfunction "Q1_1") (pintype "passive"))
    )
    (net (code "73") (name "Net-(U6-Q2)") (class "Default")
      (node (ref "R27") (pin "2") (pinfunction "2_2") (pintype "passive"))
      (node (ref "U6") (pin "2") (pinfunction "Q2_2") (pintype "passive"))
    )
    (net (code "74") (name "Net-(U6-Q3)") (class "Default")
      (node (ref "R29") (pin "2") (pinfunction "2_2") (pintype "passive"))
      (node (ref "U6") (pin "3") (pinfunction "Q3_3") (pintype "passive"))
    )
    (net (code "75") (name "Net-(U6-Q4)") (class "Default")
      (node (ref "R30") (pin "2") (pinfunction "2_2") (pintype "passive"))
      (node (ref "U6") (pin "4") (pinfunction "Q4_4") (pintype "passive"))
    )
    (net (code "76") (name "Net-(U6-Q5)") (class "Default")
      (node (ref "R31") (pin "2") (pinfunction "2_2") (pintype "passive"))
      (node (ref "U6") (pin "5") (pinfunction "Q5_5") (pintype "passive"))
    )
    (net (code "77") (name "Net-(U6-Q6)") (class "Default")
      (node (ref "R32") (pin "2") (pinfunction "2_2") (pintype "passive"))
      (node (ref "U6") (pin "6") (pinfunction "Q6_6") (pintype "passive"))
    )
    (net (code "78") (name "Net-(U6-Q7)") (class "Default")
      (node (ref "R33") (pin "2") (pinfunction "2_2") (pintype "passive"))
      (node (ref "U6") (pin "7") (pinfunction "Q7_7") (pintype "passive"))
    )
    (net (code "79") (name "Net-(U6-Q~{7})") (class "Default")
      (node (ref "U6") (pin "9") (pinfunction "Q~{7}_9") (pintype "passive"))
      (node (ref "U7") (pin "14") (pinfunction "DS_14") (pintype "passive"))
    )
    (net (code "80") (name "Net-(U7-Q0)") (class "Default")
      (node (ref "R36") (pin "1") (pinfunction "1_1") (pintype "passive"))
      (node (ref "U7") (pin "15") (pinfunction "Q0_15") (pintype "passive"))
    )
    (net (code "81") (name "Net-(U7-Q1)") (class "Default")
      (node (ref "R34") (pin "2") (pinfunction "2_2") (pintype "passive"))
      (node (ref "U7") (pin "1") (pinfunction "Q1_1") (pintype "passive"))
    )
    (net (code "82") (name "Net-(U7-Q2)") (class "Default")
      (node (ref "R35") (pin "2") (pinfunction "2_2") (pintype "passive"))
      (node (ref "U7") (pin "2") (pinfunction "Q2_2") (pintype "passive"))
    )
    (net (code "83") (name "Net-(U7-Q3)") (class "Default")
      (node (ref "R37") (pin "2") (pinfunction "2_2") (pintype "passive"))
      (node (ref "U7") (pin "3") (pinfunction "Q3_3") (pintype "passive"))
    )
    (net (code "84") (name "Net-(U7-Q4)") (class "Default")
      (node (ref "R38") (pin "2") (pinfunction "2_2") (pintype "passive"))
      (node (ref "U7") (pin "4") (pinfunction "Q4_4") (pintype "passive"))
    )
    (net (code "85") (name "Net-(U7-Q5)") (class "Default")
      (node (ref "R39") (pin "2") (pinfunction "2_2") (pintype "passive"))
      (node (ref "U7") (pin "5") (pinfunction "Q5_5") (pintype "passive"))
    )
    (net (code "86") (name "Net-(U7-Q6)") (class "Default")
      (node (ref "R40") (pin "2") (pinfunction "2_2") (pintype "passive"))
      (node (ref "U7") (pin "6") (pinfunction "Q6_6") (pintype "passive"))
    )
    (net (code "87") (name "Net-(U7-Q7)") (class "Default")
      (node (ref "R41") (pin "2") (pinfunction "2_2") (pintype "passive"))
      (node (ref "U7") (pin "7") (pinfunction "Q7_7") (pintype "passive"))
    )
    (net (code "88") (name "Net-(U7-Q~{7})") (class "Default")
      (node (ref "U7") (pin "9") (pinfunction "Q~{7}_9") (pintype "passive"))
      (node (ref "U8") (pin "14") (pinfunction "DS_14") (pintype "passive"))
    )
    (net (code "89") (name "Net-(U8-Q0)") (class "Default")
      (node (ref "R44") (pin "1") (pinfunction "1_1") (pintype "passive"))
      (node (ref "U8") (pin "15") (pinfunction "Q0_15") (pintype "passive"))
    )
    (net (code "90") (name "Net-(U8-Q1)") (class "Default")
      (node (ref "R42") (pin "2") (pinfunction "2_2") (pintype "passive"))
      (node (ref "U8") (pin "1") (pinfunction "Q1_1") (pintype "passive"))
    )
    (net (code "91") (name "Net-(U8-Q2)") (class "Default")
      (node (ref "R43") (pin "2") (pinfunction "2_2") (pintype "passive"))
      (node (ref "U8") (pin "2") (pinfunction "Q2_2") (pintype "passive"))
    )
    (net (code "92") (name "Net-(U8-Q3)") (class "Default")
      (node (ref "R45") (pin "2") (pinfunction "2_2") (pintype "passive"))
      (node (ref "U8") (pin "3") (pinfunction "Q3_3") (pintype "passive"))
    )
    (net (code "93") (name "Net-(U8-Q~{7})") (class "Default")
      (node (ref "U8") (pin "9") (pinfunction "Q~{7}_9") (pintype "passive"))
      (node (ref "U9") (pin "14") (pinfunction "DS_14") (pintype "passive"))
    )
    (net (code "94") (name "Net-(U10-IN1)") (class "Default")
      (node (ref "U10") (pin "1") (pinfunction "IN1_1") (pintype "passive"))
      (node (ref "U9") (pin "7") (pinfunction "Q7_7") (pintype "passive"))
    )
    (net (code "95") (name "Net-(U10-IN2)") (class "Default")
      (node (ref "U10") (pin "2") (pinfunction "IN2_2") (pintype "passive"))
      (node (ref "U9") (pin "6") (pinfunction "Q6_6") (pintype "passive"))
    )
    (net (code "96") (name "Net-(U10-IN3)") (class "Default")
      (node (ref "U10") (pin "3") (pinfunction "IN3_3") (pintype "passive"))
      (node (ref "U9") (pin "5") (pinfunction "Q5_5") (pintype "passive"))
    )
    (net (code "97") (name "Net-(U10-IN4)") (class "Default")
      (node (ref "U10") (pin "4") (pinfunction "IN4_4") (pintype "passive"))
      (node (ref "U9") (pin "4") (pinfunction "Q4_4") (pintype "passive"))
    )
    (net (code "98") (name "Net-(U10-IN5)") (class "Default")
      (node (ref "U10") (pin "5") (pinfunction "IN5_5") (pintype "passive"))
      (node (ref "U9") (pin "3") (pinfunction "Q3_3") (pintype "passive"))
    )
    (net (code "99") (name "Net-(U10-IN6)") (class "Default")
      (node (ref "U10") (pin "6") (pinfunction "IN6_6") (pintype "passive"))
      (node (ref "U9") (pin "2") (pinfunction "Q2_2") (pintype "passive"))
    )
    (net (code "100") (name "Net-(U10-IN7)") (class "Default")
      (node (ref "U10") (pin "7") (pinfunction "IN7_7") (pintype "passive"))
      (node (ref "U9") (pin "1") (pinfunction "Q1_1") (pintype "passive"))
    )
    (net (code "101") (name "Net-(U11-DS)") (class "Default")
      (node (ref "U11") (pin "14") (pinfunction "DS_14") (pintype "passive"))
      (node (ref "U9") (pin "9") (pinfunction "Q~{7}_9") (pintype "passive"))
    )
    (net (code "102") (name "Net-(U11-Q1)") (class "Default")
      (node (ref "U11") (pin "1") (pinfunction "Q1_1") (pintype "passive"))
      (node (ref "U12") (pin "7") (pinfunction "IN7_7") (pintype "passive"))
    )
    (net (code "103") (name "Net-(U11-Q2)") (class "Default")
      (node (ref "U11") (pin "2") (pinfunction "Q2_2") (pintype "passive"))
      (node (ref "U12") (pin "6") (pinfunction "IN6_6") (pintype "passive"))
    )
    (net (code "104") (name "Net-(U11-Q3)") (class "Default")
      (node (ref "U11") (pin "3") (pinfunction "Q3_3") (pintype "passive"))
      (node (ref "U12") (pin "5") (pinfunction "IN5_5") (pintype "passive"))
    )
    (net (code "105") (name "Net-(U11-Q4)") (class "Default")
      (node (ref "U11") (pin "4") (pinfunction "Q4_4") (pintype "passive"))
      (node (ref "U12") (pin "4") (pinfunction "IN4_4") (pintype "passive"))
    )
    (net (code "106") (name "Net-(U11-Q5)") (class "Default")
      (node (ref "U11") (pin "5") (pinfunction "Q5_5") (pintype "passive"))
      (node (ref "U12") (pin "3") (pinfunction "IN3_3") (pintype "passive"))
    )
    (net (code "107") (name "Net-(U11-Q6)") (class "Default")
      (node (ref "U11") (pin "6") (pinfunction "Q6_6") (pintype "passive"))
      (node (ref "U12") (pin "2") (pinfunction "IN2_2") (pintype "passive"))
    )
    (net (code "108") (name "Net-(U11-Q7)") (class "Default")
      (node (ref "U11") (pin "7") (pinfunction "Q7_7") (pintype "passive"))
      (node (ref "U12") (pin "1") (pinfunction "IN1_1") (pintype "passive"))
    )
    (net (code "109") (name "VBUS") (class "Default")
      (node (ref "C13") (pin "1") (pinfunction "1_1") (pintype "passive"))
      (node (ref "C14") (pin "1") (pinfunction "1_1") (pintype "passive"))
      (node (ref "C15") (pin "1") (pinfunction "1_1") (pintype "passive"))
      (node (ref "C16") (pin "1") (pinfunction "1_1") (pintype "passive"))
      (node (ref "C17") (pin "1") (pinfunction "1_1") (pintype "passive"))
      (node (ref "U11") (pin "10") (pinfunction "~{MR}_10") (pintype "passive"))
      (node (ref "U11") (pin "16") (pinfunction "VCC_16") (pintype "passive"))
      (node (ref "U4") (pin "10") (pinfunction "~{MR}_10") (pintype "passive"))
      (node (ref "U4") (pin "16") (pinfunction "VCC_16") (pintype "passive"))
      (node (ref "U5") (pin "10") (pinfunction "~{MR}_10") (pintype "passive"))
      (node (ref "U5") (pin "16") (pinfunction "VCC_16") (pintype "passive"))
      (node (ref "U6") (pin "10") (pinfunction "~{MR}_10") (pintype "passive"))
      (node (ref "U6") (pin "16") (pinfunction "VCC_16") (pintype "passive"))
      (node (ref "U7") (pin "10") (pinfunction "~{MR}_10") (pintype "passive"))
      (node (ref "U7") (pin "16") (pinfunction "VCC_16") (pintype "passive"))
      (node (ref "U8") (pin "10") (pinfunction "~{MR}_10") (pintype "passive"))
      (node (ref "U8") (pin "16") (pinfunction "VCC_16") (pintype "passive"))
      (node (ref "U9") (pin "10") (pinfunction "~{MR}_10") (pintype "passive"))
      (node (ref "U9") (pin "16") (pinfunction "VCC_16") (pintype "passive"))
    )
    (net (code "110") (name "unconnected-(U8-Q4-Pad4)") (class "Default")
      (node (ref "U8") (pin "4") (pinfunction "Q4_4") (pintype "passive"))
    )
    (net (code "111") (name "unconnected-(U8-Q5-Pad5)") (class "Default")
      (node (ref "U8") (pin "5") (pinfunction "Q5_5") (pintype "passive"))
    )
    (net (code "112") (name "unconnected-(U8-Q6-Pad6)") (class "Default")
      (node (ref "U8") (pin "6") (pinfunction "Q6_6") (pintype "passive"))
    )
    (net (code "113") (name "unconnected-(U8-Q7-Pad7)") (class "Default")
      (node (ref "U8") (pin "7") (pinfunction "Q7_7") (pintype "passive"))
    )
    (net (code "114") (name "unconnected-(U9-Q0-Pad15)") (class "Default")
      (node (ref "U9") (pin "15") (pinfunction "Q0_15") (pintype "passive"))
    )
    (net (code "115") (name "unconnected-(U10-COM-Pad9)") (class "Default")
      (node (ref "U10") (pin "9") (pinfunction "COM_9") (pintype "passive"))
    )
    (net (code "116") (name "unconnected-(U10-OUT1-Pad16)") (class "Default")
      (node (ref "U10") (pin "16") (pinfunction "OUT1_16") (pintype "passive"))
    )
    (net (code "117") (name "unconnected-(U10-OUT2-Pad15)") (class "Default")
      (node (ref "U10") (pin "15") (pinfunction "OUT2_15") (pintype "passive"))
    )
    (net (code "118") (name "unconnected-(U11-Q0-Pad15)") (class "Default")
      (node (ref "U11") (pin "15") (pinfunction "Q0_15") (pintype "passive"))
    )
    (net (code "119") (name "unconnected-(U11-Q~{7}-Pad9)") (class "Default")
      (node (ref "U11") (pin "9") (pinfunction "Q~{7}_9") (pintype "passive"))
    )
    (net (code "120") (name "unconnected-(U12-COM-Pad9)") (class "Default")
      (node (ref "U12") (pin "9") (pinfunction "COM_9") (pintype "passive"))
    )
  )
)
